# LEDSyncDRVG2.net
KiCad netlist of a schematic drawn in EAGLE
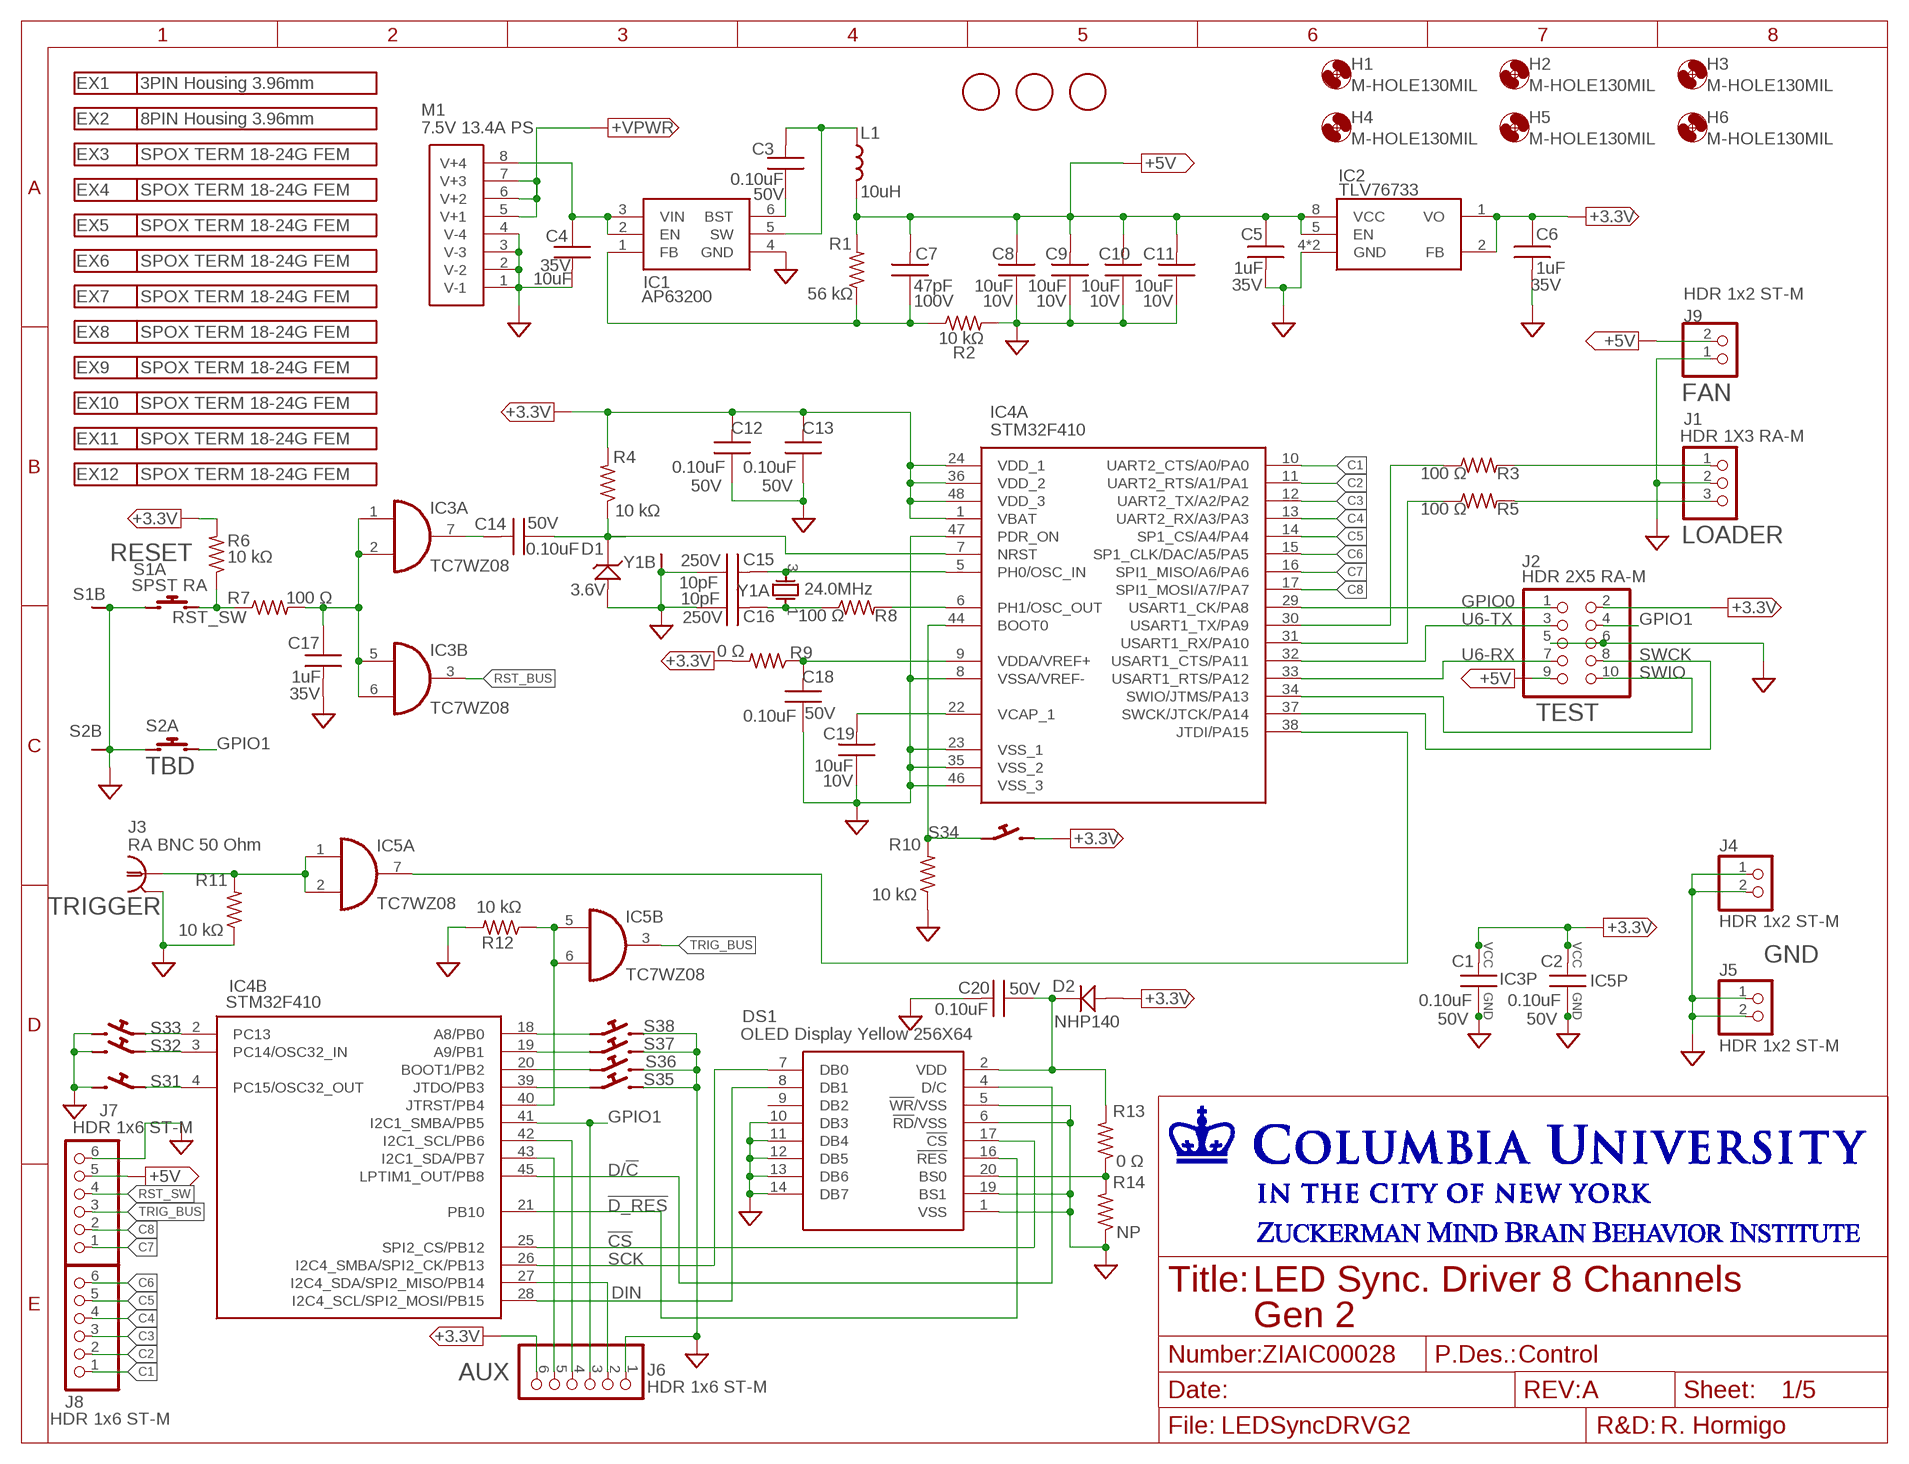
[diagram p0: schematic, sheet 1]
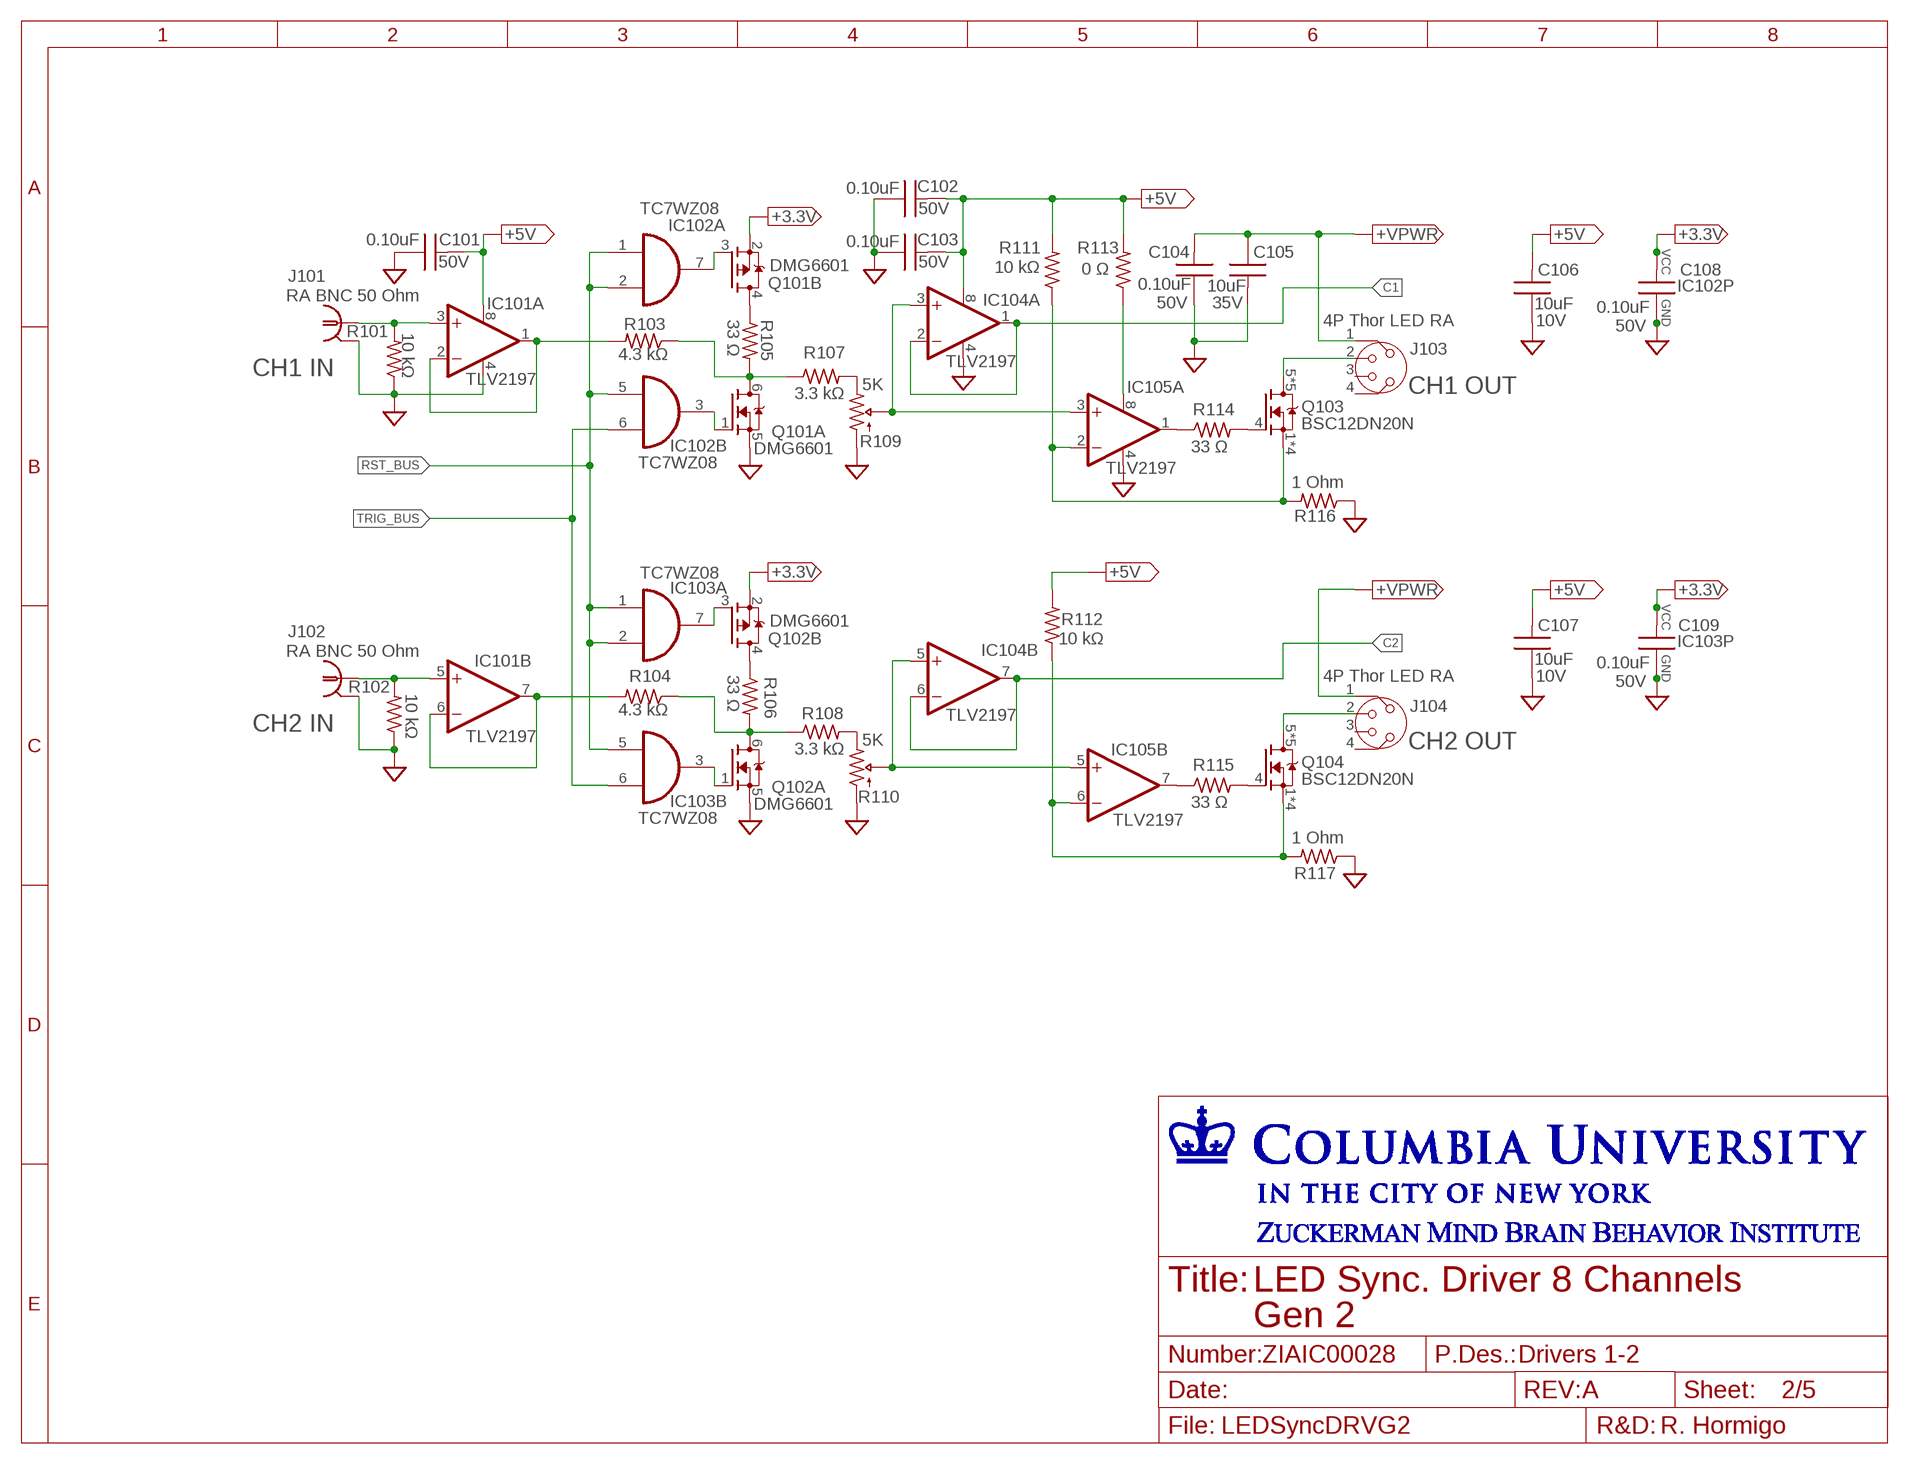
[diagram p1: schematic, sheet 2]
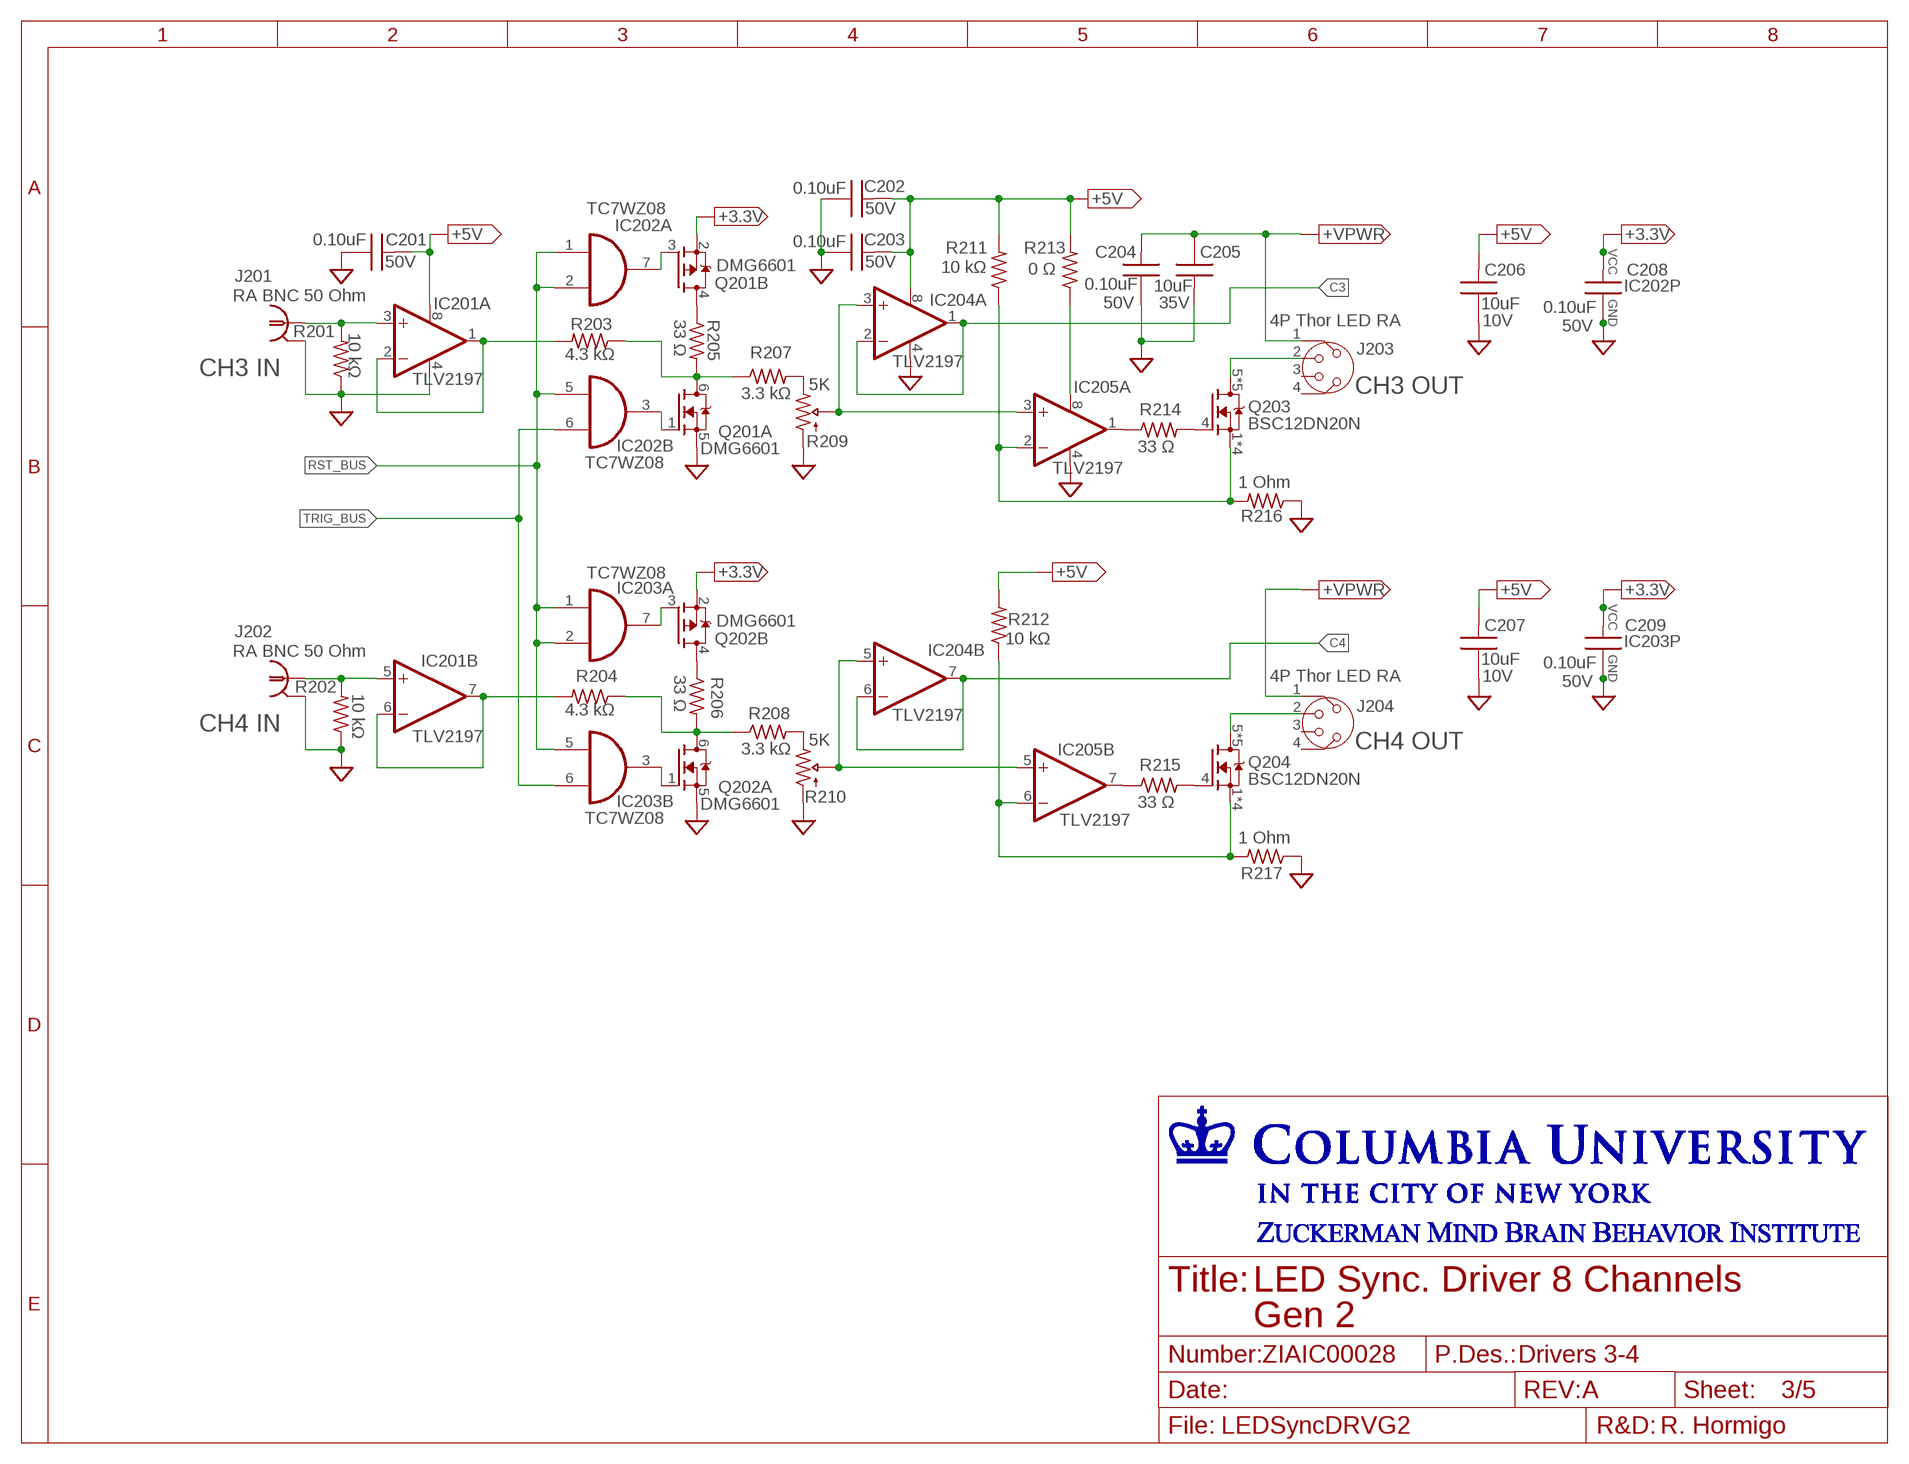
[diagram p2: schematic, sheet 3]
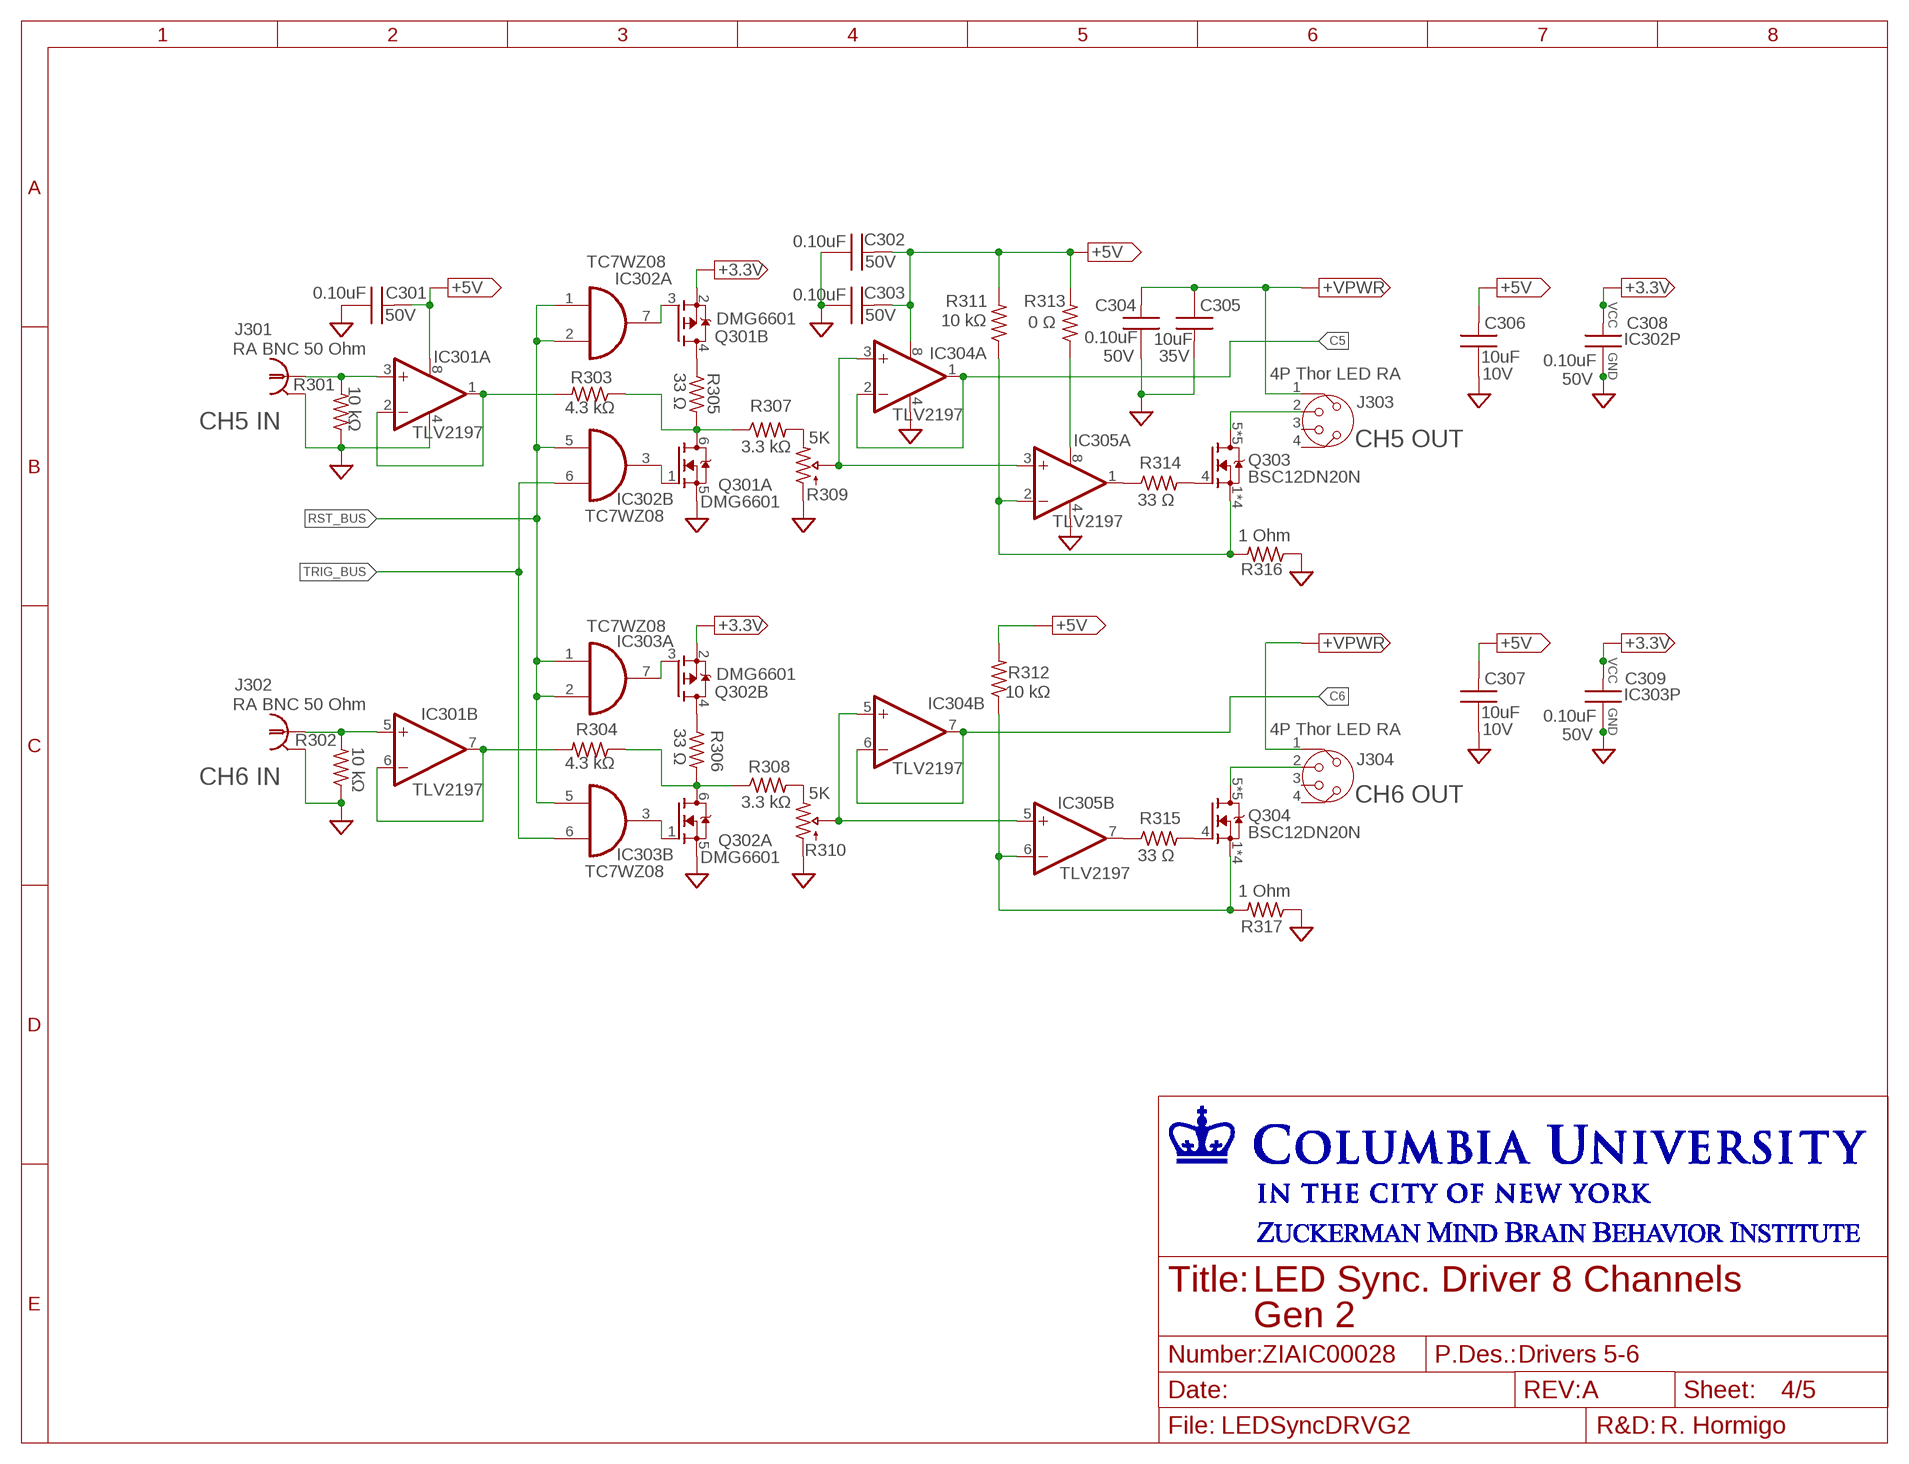
[diagram p3: schematic, sheet 4]
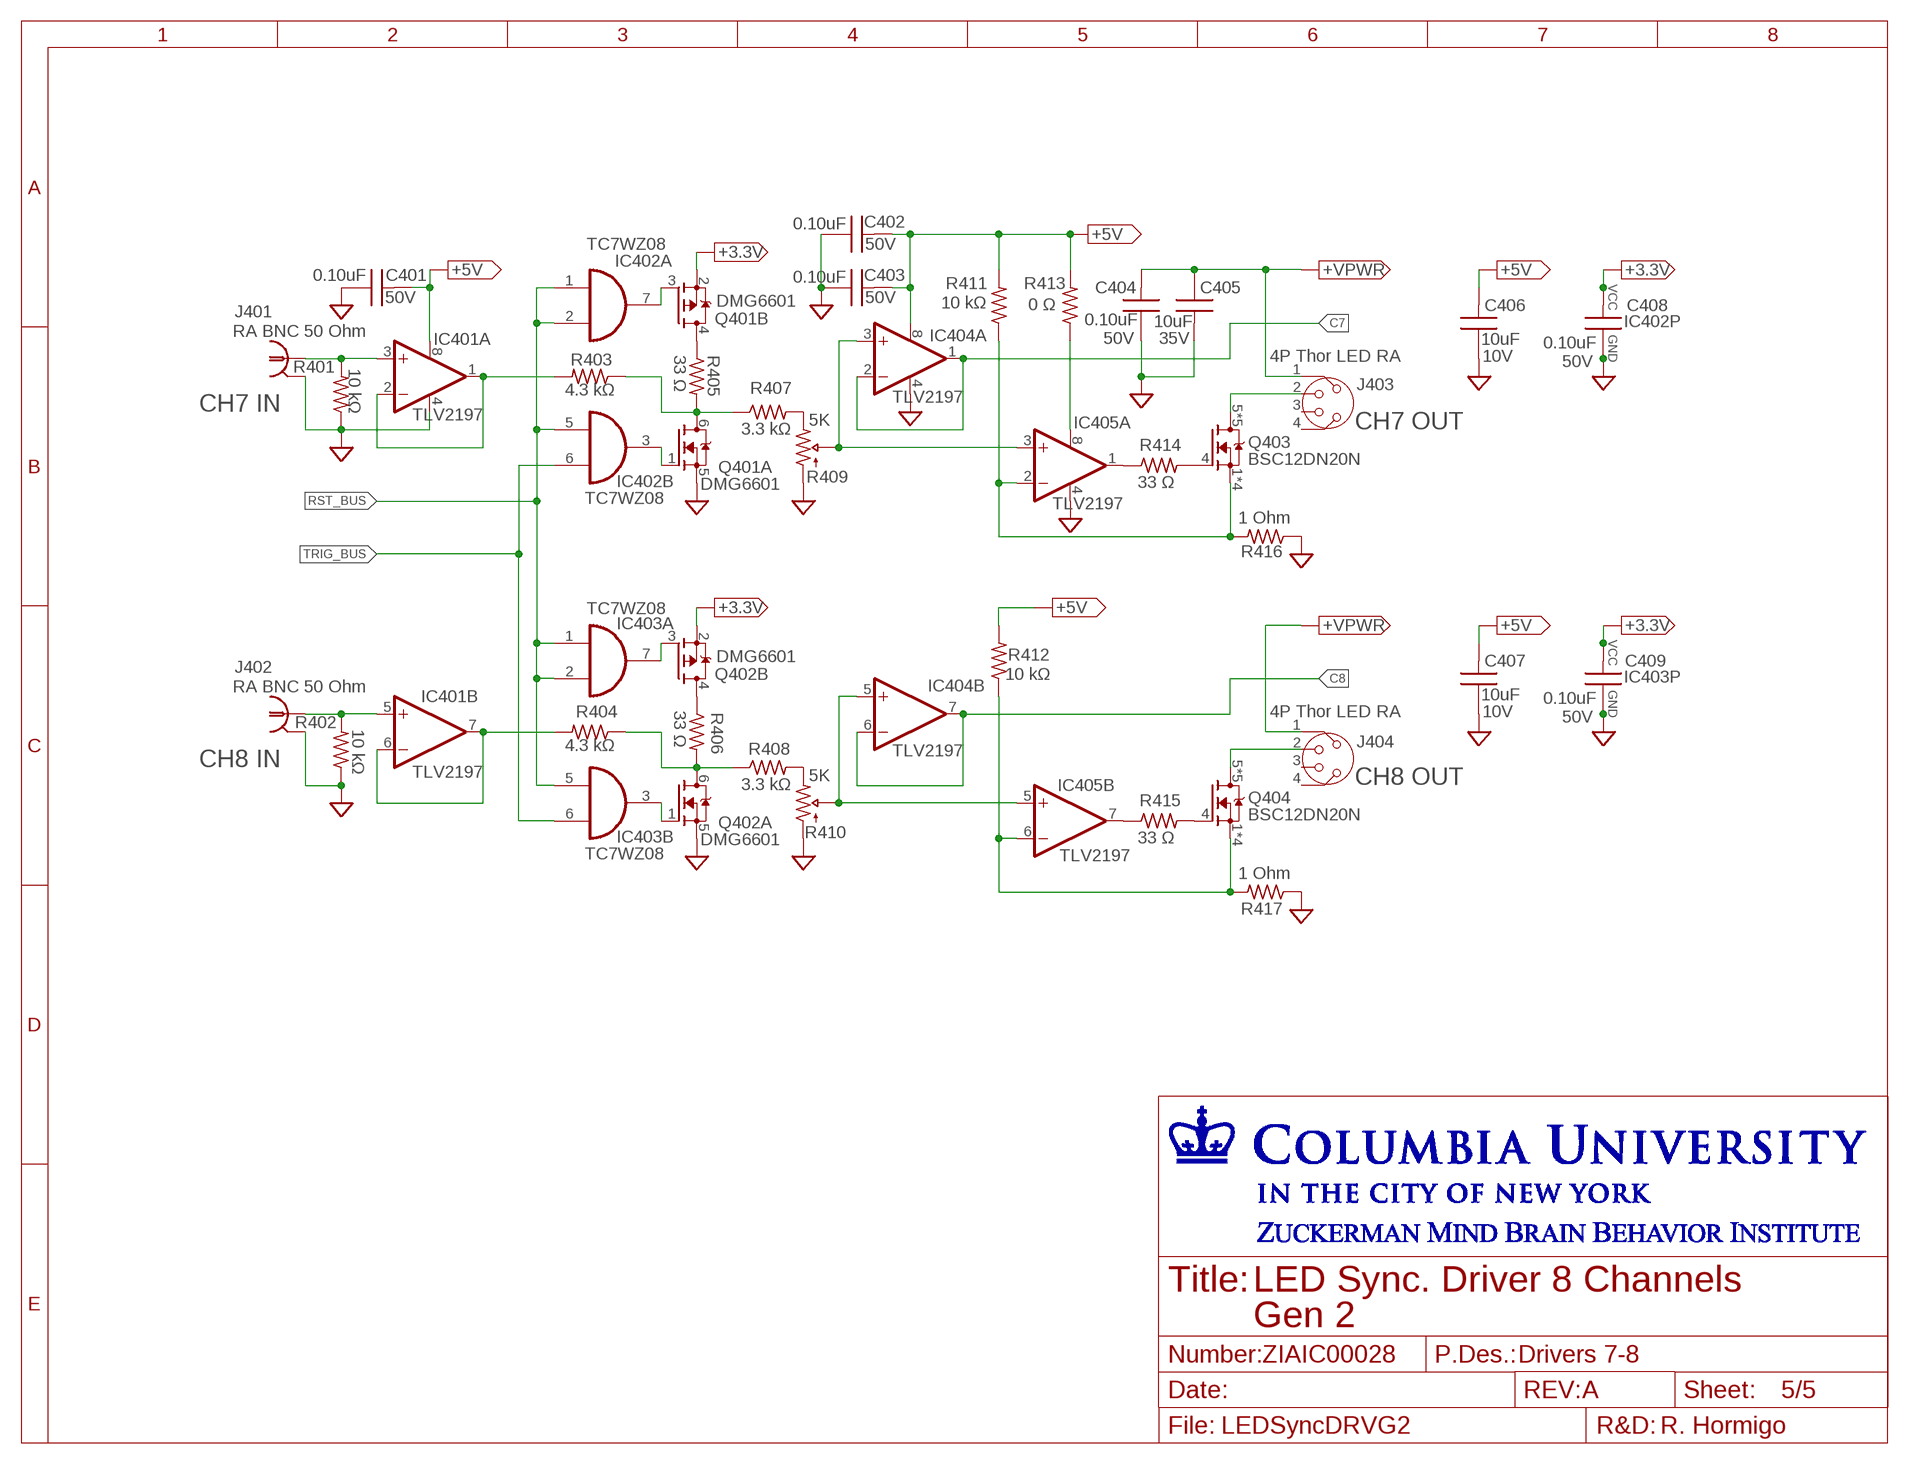
[diagram p4: schematic, sheet 5]

(export (version "E")
  (design (tool "Eeschema 10.0.6"))
  (components
    (comp (ref "C101")
      (value "0.10uF")
      (footprint "eagle-import:MLCC_0603")
      (fields
        (field (name "MPN") "06035C104JAT2A")
        (field (name "TOLERANCE") "5%")
        (field (name "VOLTAGE") "50V")
      )
      (libsource (lib "eagle-import") (part "MLCC_0603_100N"))
    )
    (comp (ref "C102")
      (value "0.10uF")
      (footprint "eagle-import:MLCC_0603")
      (fields
        (field (name "MPN") "06035C104JAT2A")
        (field (name "TOLERANCE") "5%")
        (field (name "VOLTAGE") "50V")
      )
      (libsource (lib "eagle-import") (part "MLCC_0603_100N"))
    )
    (comp (ref "C103")
      (value "0.10uF")
      (footprint "eagle-import:MLCC_0603")
      (fields
        (field (name "MPN") "06035C104JAT2A")
        (field (name "TOLERANCE") "5%")
        (field (name "VOLTAGE") "50V")
      )
      (libsource (lib "eagle-import") (part "MLCC_0603_100N"))
    )
    (comp (ref "C104")
      (value "0.10uF")
      (footprint "eagle-import:MLCC_0603")
      (fields
        (field (name "MPN") "06035C104JAT2A")
        (field (name "TOLERANCE") "5%")
        (field (name "VOLTAGE") "50V")
      )
      (libsource (lib "eagle-import") (part "MLCC_0603_100N"))
    )
    (comp (ref "C105")
      (value "10uF")
      (footprint "eagle-import:MLCC_1206")
      (fields (field (name "VOLTAGE") "35V") (field (name "MPN") "GMK316AB7106KL-TR"))
      (libsource (lib "eagle-import") (part "MLCC1206_"))
    )
    (comp (ref "C106")
      (value "10uF")
      (footprint "eagle-import:MLCC_0603")
      (fields
        (field (name "MPN") "0603ZD106KAT2A")
        (field (name "TOLERANCE") "10%")
        (field (name "VOLTAGE") "10V")
      )
      (libsource (lib "eagle-import") (part "MLCC_0603_10UF-10V"))
    )
    (comp (ref "C107")
      (value "10uF")
      (footprint "eagle-import:MLCC_0603")
      (fields
        (field (name "MPN") "0603ZD106KAT2A")
        (field (name "TOLERANCE") "10%")
        (field (name "VOLTAGE") "10V")
      )
      (libsource (lib "eagle-import") (part "MLCC_0603_10UF-10V"))
    )
    (comp (ref "C108")
      (value "0.10uF")
      (footprint "eagle-import:MLCC_0603")
      (fields
        (field (name "MPN") "06035C104JAT2A")
        (field (name "TOLERANCE") "5%")
        (field (name "VOLTAGE") "50V")
      )
      (libsource (lib "eagle-import") (part "MLCC_0603_100N"))
    )
    (comp (ref "C109")
      (value "0.10uF")
      (footprint "eagle-import:MLCC_0603")
      (fields
        (field (name "MPN") "06035C104JAT2A")
        (field (name "TOLERANCE") "5%")
        (field (name "VOLTAGE") "50V")
      )
      (libsource (lib "eagle-import") (part "MLCC_0603_100N"))
    )
    (comp (ref "IC101")
      (value "TLV2197")
      (footprint "eagle-import:VSSOP8-DGK-065P")
      (fields (field (name "MPN") "TLV2197QDGKRQ1"))
      (libsource (lib "eagle-import") (part "OPA_D_TLV2172IDGKRTLV2197QDGK"))
    )
    (comp (ref "IC102")
      (value "TC7WZ08")
      (footprint "eagle-import:SOP50P310X90-8N")
      (fields (field (name "MPN") "TC7WZ08FK"))
      (libsource (lib "eagle-import") (part "AND2_TSOP8"))
    )
    (comp (ref "IC103")
      (value "TC7WZ08")
      (footprint "eagle-import:SOP50P310X90-8N")
      (fields (field (name "MPN") "TC7WZ08FK"))
      (libsource (lib "eagle-import") (part "AND2_TSOP8"))
    )
    (comp (ref "IC104")
      (value "TLV2197")
      (footprint "eagle-import:VSSOP8-DGK-065P")
      (fields (field (name "MPN") "TLV2197QDGKRQ1"))
      (libsource (lib "eagle-import") (part "OPA_D_TLV2172IDGKRTLV2197QDGK"))
    )
    (comp (ref "IC105")
      (value "TLV2197")
      (footprint "eagle-import:VSSOP8-DGK-065P")
      (fields (field (name "MPN") "TLV2197QDGKRQ1"))
      (libsource (lib "eagle-import") (part "OPA_D_TLV2172IDGKRTLV2197QDGK"))
    )
    (comp (ref "J101")
      (value "RA BNC 50 Ohm")
      (footprint "eagle-import:BNC_AMP_227161")
      (fields (field (name "MPN") "5227161-6"))
      (libsource (lib "eagle-import") (part "BNC-4P"))
    )
    (comp (ref "J102")
      (value "RA BNC 50 Ohm")
      (footprint "eagle-import:BNC_AMP_227161")
      (fields (field (name "MPN") "5227161-6"))
      (libsource (lib "eagle-import") (part "BNC-4P"))
    )
    (comp (ref "J103")
      (value "4P Thor LED RA")
      (footprint "eagle-import:CIR_PHX4P_RA")
      (fields (field (name "MPN") "1526169"))
      (libsource (lib "eagle-import") (part "CIRCULAR-4P-THOR-F"))
    )
    (comp (ref "J104")
      (value "4P Thor LED RA")
      (footprint "eagle-import:CIR_PHX4P_RA")
      (fields (field (name "MPN") "1526169"))
      (libsource (lib "eagle-import") (part "CIRCULAR-4P-THOR-F"))
    )
    (comp (ref "Q101")
      (value "DMG6601")
      (footprint "eagle-import:SOT95P280X100-6N")
      (fields (field (name "MPN") "DMG6601LVT-7"))
      (libsource (lib "eagle-import") (part "MOSFET-PN"))
    )
    (comp (ref "Q102")
      (value "DMG6601")
      (footprint "eagle-import:SOT95P280X100-6N")
      (fields (field (name "MPN") "DMG6601LVT-7"))
      (libsource (lib "eagle-import") (part "MOSFET-PN"))
    )
    (comp (ref "Q103")
      (value "BSC12DN20N")
      (footprint "eagle-import:TDSON-8")
      (fields (field (name "MPN") "BSC12DN20NS3 G") (field (name "POWER") "50W"))
      (libsource (lib "eagle-import") (part "MOSFET-NN-MOSFETBSC12DN20NS3G"))
    )
    (comp (ref "Q104")
      (value "BSC12DN20N")
      (footprint "eagle-import:TDSON-8")
      (fields (field (name "MPN") "BSC12DN20NS3 G") (field (name "POWER") "50W"))
      (libsource (lib "eagle-import") (part "MOSFET-NN-MOSFETBSC12DN20NS3G"))
    )
    (comp (ref "R101")
      (value "10 kΩ")
      (footprint "eagle-import:R0603")
      (fields
        (field (name "MPN") "CRCW060310K0FKEA")
        (field (name "POWER") "0.1W")
        (field (name "TOLERANCE") "1%")
      )
      (libsource (lib "eagle-import") (part "RES_0603_10K0"))
    )
    (comp (ref "R102")
      (value "10 kΩ")
      (footprint "eagle-import:R0603")
      (fields
        (field (name "MPN") "CRCW060310K0FKEA")
        (field (name "POWER") "0.1W")
        (field (name "TOLERANCE") "1%")
      )
      (libsource (lib "eagle-import") (part "RES_0603_10K0"))
    )
    (comp (ref "R103")
      (value "4.3 kΩ")
      (footprint "eagle-import:R0603")
      (fields
        (field (name "MPN") "CRCW06034K30FKEA")
        (field (name "POWER") "0.1W")
        (field (name "TOLERANCE") "1%")
      )
      (libsource (lib "eagle-import") (part "RES_0603_4K30"))
    )
    (comp (ref "R104")
      (value "4.3 kΩ")
      (footprint "eagle-import:R0603")
      (fields
        (field (name "MPN") "CRCW06034K30FKEA")
        (field (name "POWER") "0.1W")
        (field (name "TOLERANCE") "1%")
      )
      (libsource (lib "eagle-import") (part "RES_0603_4K30"))
    )
    (comp (ref "R105")
      (value "33 Ω")
      (footprint "eagle-import:R0603")
      (fields
        (field (name "MPN") "CRCW060333R0FKEA")
        (field (name "POWER") "0.1W")
        (field (name "TOLERANCE") "1%")
      )
      (libsource (lib "eagle-import") (part "RES_0603_33R0"))
    )
    (comp (ref "R106")
      (value "33 Ω")
      (footprint "eagle-import:R0603")
      (fields
        (field (name "MPN") "CRCW060333R0FKEA")
        (field (name "POWER") "0.1W")
        (field (name "TOLERANCE") "1%")
      )
      (libsource (lib "eagle-import") (part "RES_0603_33R0"))
    )
    (comp (ref "R107")
      (value "3.3 kΩ")
      (footprint "eagle-import:R0603")
      (fields
        (field (name "MPN") "CRCW06033K30FKEA")
        (field (name "POWER") "0.1W")
        (field (name "TOLERANCE") "1%")
      )
      (libsource (lib "eagle-import") (part "RES_0603_3K30"))
    )
    (comp (ref "R108")
      (value "3.3 kΩ")
      (footprint "eagle-import:R0603")
      (fields
        (field (name "MPN") "CRCW06033K30FKEA")
        (field (name "POWER") "0.1W")
        (field (name "TOLERANCE") "1%")
      )
      (libsource (lib "eagle-import") (part "RES_0603_3K30"))
    )
    (comp (ref "R109")
      (value "5K")
      (footprint "eagle-import:MTBOURNS_RA_LONG")
      (fields (field (name "MPN") "3006P-7-502LF"))
      (libsource (lib "eagle-import") (part "RES_TRIM_5K_RA_MTURN"))
    )
    (comp (ref "R110")
      (value "5K")
      (footprint "eagle-import:MTBOURNS_RA_LONG")
      (fields (field (name "MPN") "3006P-7-502LF"))
      (libsource (lib "eagle-import") (part "RES_TRIM_5K_RA_MTURN"))
    )
    (comp (ref "R111")
      (value "10 kΩ")
      (footprint "eagle-import:R0603")
      (fields
        (field (name "MPN") "CRCW060310K0FKEA")
        (field (name "POWER") "0.1W")
        (field (name "TOLERANCE") "1%")
      )
      (libsource (lib "eagle-import") (part "RES_0603_10K0"))
    )
    (comp (ref "R112")
      (value "10 kΩ")
      (footprint "eagle-import:R0603")
      (fields
        (field (name "MPN") "CRCW060310K0FKEA")
        (field (name "POWER") "0.1W")
        (field (name "TOLERANCE") "1%")
      )
      (libsource (lib "eagle-import") (part "RES_0603_10K0"))
    )
    (comp (ref "R113")
      (value "0 Ω")
      (footprint "eagle-import:R0603")
      (fields (field (name "MPN") "CRCW06030000Z0EA"))
      (libsource (lib "eagle-import") (part "RES_0603_0000"))
    )
    (comp (ref "R114")
      (value "33 Ω")
      (footprint "eagle-import:R0603")
      (fields
        (field (name "MPN") "CRCW060333R0FKEA")
        (field (name "POWER") "0.1W")
        (field (name "TOLERANCE") "1%")
      )
      (libsource (lib "eagle-import") (part "RES_0603_33R0"))
    )
    (comp (ref "R115")
      (value "33 Ω")
      (footprint "eagle-import:R0603")
      (fields
        (field (name "MPN") "CRCW060333R0FKEA")
        (field (name "POWER") "0.1W")
        (field (name "TOLERANCE") "1%")
      )
      (libsource (lib "eagle-import") (part "RES_0603_33R0"))
    )
    (comp (ref "R116")
      (value "1 Ohm")
      (footprint "eagle-import:R1225")
      (fields (field (name "MPN") "WK73S3A3TTE1R00F"))
      (libsource (lib "eagle-import") (part "RES_1225_"))
    )
    (comp (ref "R117")
      (value "1 Ohm")
      (footprint "eagle-import:R1225")
      (fields (field (name "MPN") "WK73S3A3TTE1R00F"))
      (libsource (lib "eagle-import") (part "RES_1225_"))
    )
    (comp (ref "C301")
      (value "0.10uF")
      (footprint "eagle-import:MLCC_0603")
      (fields
        (field (name "MPN") "06035C104JAT2A")
        (field (name "TOLERANCE") "5%")
        (field (name "VOLTAGE") "50V")
      )
      (libsource (lib "eagle-import") (part "MLCC_0603_100N"))
    )
    (comp (ref "C302")
      (value "0.10uF")
      (footprint "eagle-import:MLCC_0603")
      (fields
        (field (name "MPN") "06035C104JAT2A")
        (field (name "TOLERANCE") "5%")
        (field (name "VOLTAGE") "50V")
      )
      (libsource (lib "eagle-import") (part "MLCC_0603_100N"))
    )
    (comp (ref "C303")
      (value "0.10uF")
      (footprint "eagle-import:MLCC_0603")
      (fields
        (field (name "MPN") "06035C104JAT2A")
        (field (name "TOLERANCE") "5%")
        (field (name "VOLTAGE") "50V")
      )
      (libsource (lib "eagle-import") (part "MLCC_0603_100N"))
    )
    (comp (ref "C304")
      (value "0.10uF")
      (footprint "eagle-import:MLCC_0603")
      (fields
        (field (name "MPN") "06035C104JAT2A")
        (field (name "TOLERANCE") "5%")
        (field (name "VOLTAGE") "50V")
      )
      (libsource (lib "eagle-import") (part "MLCC_0603_100N"))
    )
    (comp (ref "C305")
      (value "10uF")
      (footprint "eagle-import:MLCC_1206")
      (fields (field (name "VOLTAGE") "35V") (field (name "MPN") "GMK316AB7106KL-TR"))
      (libsource (lib "eagle-import") (part "MLCC1206_"))
    )
    (comp (ref "C306")
      (value "10uF")
      (footprint "eagle-import:MLCC_0603")
      (fields
        (field (name "MPN") "0603ZD106KAT2A")
        (field (name "TOLERANCE") "10%")
        (field (name "VOLTAGE") "10V")
      )
      (libsource (lib "eagle-import") (part "MLCC_0603_10UF-10V"))
    )
    (comp (ref "C307")
      (value "10uF")
      (footprint "eagle-import:MLCC_0603")
      (fields
        (field (name "MPN") "0603ZD106KAT2A")
        (field (name "TOLERANCE") "10%")
        (field (name "VOLTAGE") "10V")
      )
      (libsource (lib "eagle-import") (part "MLCC_0603_10UF-10V"))
    )
    (comp (ref "C308")
      (value "0.10uF")
      (footprint "eagle-import:MLCC_0603")
      (fields
        (field (name "MPN") "06035C104JAT2A")
        (field (name "TOLERANCE") "5%")
        (field (name "VOLTAGE") "50V")
      )
      (libsource (lib "eagle-import") (part "MLCC_0603_100N"))
    )
    (comp (ref "C309")
      (value "0.10uF")
      (footprint "eagle-import:MLCC_0603")
      (fields
        (field (name "MPN") "06035C104JAT2A")
        (field (name "TOLERANCE") "5%")
        (field (name "VOLTAGE") "50V")
      )
      (libsource (lib "eagle-import") (part "MLCC_0603_100N"))
    )
    (comp (ref "IC301")
      (value "TLV2197")
      (footprint "eagle-import:VSSOP8-DGK-065P")
      (fields (field (name "MPN") "TLV2197QDGKRQ1"))
      (libsource (lib "eagle-import") (part "OPA_D_TLV2172IDGKRTLV2197QDGK"))
    )
    (comp (ref "IC302")
      (value "TC7WZ08")
      (footprint "eagle-import:SOP50P310X90-8N")
      (fields (field (name "MPN") "TC7WZ08FK"))
      (libsource (lib "eagle-import") (part "AND2_TSOP8"))
    )
    (comp (ref "IC303")
      (value "TC7WZ08")
      (footprint "eagle-import:SOP50P310X90-8N")
      (fields (field (name "MPN") "TC7WZ08FK"))
      (libsource (lib "eagle-import") (part "AND2_TSOP8"))
    )
    (comp (ref "IC304")
      (value "TLV2197")
      (footprint "eagle-import:VSSOP8-DGK-065P")
      (fields (field (name "MPN") "TLV2197QDGKRQ1"))
      (libsource (lib "eagle-import") (part "OPA_D_TLV2172IDGKRTLV2197QDGK"))
    )
    (comp (ref "IC305")
      (value "TLV2197")
      (footprint "eagle-import:VSSOP8-DGK-065P")
      (fields (field (name "MPN") "TLV2197QDGKRQ1"))
      (libsource (lib "eagle-import") (part "OPA_D_TLV2172IDGKRTLV2197QDGK"))
    )
    (comp (ref "J301")
      (value "RA BNC 50 Ohm")
      (footprint "eagle-import:BNC_AMP_227161")
      (fields (field (name "MPN") "5227161-6"))
      (libsource (lib "eagle-import") (part "BNC-4P"))
    )
    (comp (ref "J302")
      (value "RA BNC 50 Ohm")
      (footprint "eagle-import:BNC_AMP_227161")
      (fields (field (name "MPN") "5227161-6"))
      (libsource (lib "eagle-import") (part "BNC-4P"))
    )
    (comp (ref "J303")
      (value "4P Thor LED RA")
      (footprint "eagle-import:CIR_PHX4P_RA")
      (fields (field (name "MPN") "1526169"))
      (libsource (lib "eagle-import") (part "CIRCULAR-4P-THOR-F"))
    )
    (comp (ref "J304")
      (value "4P Thor LED RA")
      (footprint "eagle-import:CIR_PHX4P_RA")
      (fields (field (name "MPN") "1526169"))
      (libsource (lib "eagle-import") (part "CIRCULAR-4P-THOR-F"))
    )
    (comp (ref "Q301")
      (value "DMG6601")
      (footprint "eagle-import:SOT95P280X100-6N")
      (fields (field (name "MPN") "DMG6601LVT-7"))
      (libsource (lib "eagle-import") (part "MOSFET-PN"))
    )
    (comp (ref "Q302")
      (value "DMG6601")
      (footprint "eagle-import:SOT95P280X100-6N")
      (fields (field (name "MPN") "DMG6601LVT-7"))
      (libsource (lib "eagle-import") (part "MOSFET-PN"))
    )
    (comp (ref "Q303")
      (value "BSC12DN20N")
      (footprint "eagle-import:TDSON-8")
      (fields (field (name "MPN") "BSC12DN20NS3 G") (field (name "POWER") "50W"))
      (libsource (lib "eagle-import") (part "MOSFET-NN-MOSFETBSC12DN20NS3G"))
    )
    (comp (ref "Q304")
      (value "BSC12DN20N")
      (footprint "eagle-import:TDSON-8")
      (fields (field (name "MPN") "BSC12DN20NS3 G") (field (name "POWER") "50W"))
      (libsource (lib "eagle-import") (part "MOSFET-NN-MOSFETBSC12DN20NS3G"))
    )
    (comp (ref "R301")
      (value "10 kΩ")
      (footprint "eagle-import:R0603")
      (fields
        (field (name "MPN") "CRCW060310K0FKEA")
        (field (name "POWER") "0.1W")
        (field (name "TOLERANCE") "1%")
      )
      (libsource (lib "eagle-import") (part "RES_0603_10K0"))
    )
    (comp (ref "R302")
      (value "10 kΩ")
      (footprint "eagle-import:R0603")
      (fields
        (field (name "MPN") "CRCW060310K0FKEA")
        (field (name "POWER") "0.1W")
        (field (name "TOLERANCE") "1%")
      )
      (libsource (lib "eagle-import") (part "RES_0603_10K0"))
    )
    (comp (ref "R303")
      (value "4.3 kΩ")
      (footprint "eagle-import:R0603")
      (fields
        (field (name "MPN") "CRCW06034K30FKEA")
        (field (name "POWER") "0.1W")
        (field (name "TOLERANCE") "1%")
      )
      (libsource (lib "eagle-import") (part "RES_0603_4K30"))
    )
    (comp (ref "R304")
      (value "4.3 kΩ")
      (footprint "eagle-import:R0603")
      (fields
        (field (name "MPN") "CRCW06034K30FKEA")
        (field (name "POWER") "0.1W")
        (field (name "TOLERANCE") "1%")
      )
      (libsource (lib "eagle-import") (part "RES_0603_4K30"))
    )
    (comp (ref "R305")
      (value "33 Ω")
      (footprint "eagle-import:R0603")
      (fields
        (field (name "MPN") "CRCW060333R0FKEA")
        (field (name "POWER") "0.1W")
        (field (name "TOLERANCE") "1%")
      )
      (libsource (lib "eagle-import") (part "RES_0603_33R0"))
    )
    (comp (ref "R306")
      (value "33 Ω")
      (footprint "eagle-import:R0603")
      (fields
        (field (name "MPN") "CRCW060333R0FKEA")
        (field (name "POWER") "0.1W")
        (field (name "TOLERANCE") "1%")
      )
      (libsource (lib "eagle-import") (part "RES_0603_33R0"))
    )
    (comp (ref "R307")
      (value "3.3 kΩ")
      (footprint "eagle-import:R0603")
      (fields
        (field (name "MPN") "CRCW06033K30FKEA")
        (field (name "POWER") "0.1W")
        (field (name "TOLERANCE") "1%")
      )
      (libsource (lib "eagle-import") (part "RES_0603_3K30"))
    )
    (comp (ref "R308")
      (value "3.3 kΩ")
      (footprint "eagle-import:R0603")
      (fields
        (field (name "MPN") "CRCW06033K30FKEA")
        (field (name "POWER") "0.1W")
        (field (name "TOLERANCE") "1%")
      )
      (libsource (lib "eagle-import") (part "RES_0603_3K30"))
    )
    (comp (ref "R309")
      (value "5K")
      (footprint "eagle-import:MTBOURNS_RA_LONG")
      (fields (field (name "MPN") "3006P-7-502LF"))
      (libsource (lib "eagle-import") (part "RES_TRIM_5K_RA_MTURN"))
    )
    (comp (ref "R310")
      (value "5K")
      (footprint "eagle-import:MTBOURNS_RA_LONG")
      (fields (field (name "MPN") "3006P-7-502LF"))
      (libsource (lib "eagle-import") (part "RES_TRIM_5K_RA_MTURN"))
    )
    (comp (ref "R311")
      (value "10 kΩ")
      (footprint "eagle-import:R0603")
      (fields
        (field (name "MPN") "CRCW060310K0FKEA")
        (field (name "POWER") "0.1W")
        (field (name "TOLERANCE") "1%")
      )
      (libsource (lib "eagle-import") (part "RES_0603_10K0"))
    )
    (comp (ref "R312")
      (value "10 kΩ")
      (footprint "eagle-import:R0603")
      (fields
        (field (name "MPN") "CRCW060310K0FKEA")
        (field (name "POWER") "0.1W")
        (field (name "TOLERANCE") "1%")
      )
      (libsource (lib "eagle-import") (part "RES_0603_10K0"))
    )
    (comp (ref "R313")
      (value "0 Ω")
      (footprint "eagle-import:R0603")
      (fields (field (name "MPN") "CRCW06030000Z0EA"))
      (libsource (lib "eagle-import") (part "RES_0603_0000"))
    )
    (comp (ref "R314")
      (value "33 Ω")
      (footprint "eagle-import:R0603")
      (fields
        (field (name "MPN") "CRCW060333R0FKEA")
        (field (name "POWER") "0.1W")
        (field (name "TOLERANCE") "1%")
      )
      (libsource (lib "eagle-import") (part "RES_0603_33R0"))
    )
    (comp (ref "R315")
      (value "33 Ω")
      (footprint "eagle-import:R0603")
      (fields
        (field (name "MPN") "CRCW060333R0FKEA")
        (field (name "POWER") "0.1W")
        (field (name "TOLERANCE") "1%")
      )
      (libsource (lib "eagle-import") (part "RES_0603_33R0"))
    )
    (comp (ref "R316")
      (value "1 Ohm")
      (footprint "eagle-import:R1225")
      (fields (field (name "MPN") "WK73S3A3TTE1R00F"))
      (libsource (lib "eagle-import") (part "RES_1225_"))
    )
    (comp (ref "R317")
      (value "1 Ohm")
      (footprint "eagle-import:R1225")
      (fields (field (name "MPN") "WK73S3A3TTE1R00F"))
      (libsource (lib "eagle-import") (part "RES_1225_"))
    )
    (comp (ref "C1")
      (value "0.10uF")
      (footprint "eagle-import:MLCC_0603")
      (fields
        (field (name "MPN") "06035C104JAT2A")
        (field (name "TOLERANCE") "5%")
        (field (name "VOLTAGE") "50V")
      )
      (libsource (lib "eagle-import") (part "MLCC_0603_100N"))
    )
    (comp (ref "C2")
      (value "0.10uF")
      (footprint "eagle-import:MLCC_0603")
      (fields
        (field (name "MPN") "06035C104JAT2A")
        (field (name "TOLERANCE") "5%")
        (field (name "VOLTAGE") "50V")
      )
      (libsource (lib "eagle-import") (part "MLCC_0603_100N"))
    )
    (comp (ref "C3")
      (value "0.10uF")
      (footprint "eagle-import:MLCC_0603")
      (fields
        (field (name "MPN") "06035C104JAT2A")
        (field (name "TOLERANCE") "5%")
        (field (name "VOLTAGE") "50V")
      )
      (libsource (lib "eagle-import") (part "MLCC_0603_100N"))
    )
    (comp (ref "C4")
      (value "10uF")
      (footprint "eagle-import:MLCC_1206")
      (fields (field (name "VOLTAGE") "35V") (field (name "MPN") "GMK316AB7106KL-TR"))
      (libsource (lib "eagle-import") (part "MLCC1206_"))
    )
    (comp (ref "C5")
      (value "1uF")
      (footprint "eagle-import:MLCC_0603")
      (fields
        (field (name "MPN") "CGA3E1X7R1V105K080AC")
        (field (name "TOLERANCE") "10%")
        (field (name "VOLTAGE") "35V")
      )
      (libsource (lib "eagle-import") (part "MLCC_0603_1UF"))
    )
    (comp (ref "C6")
      (value "1uF")
      (footprint "eagle-import:MLCC_0603")
      (fields
        (field (name "MPN") "CGA3E1X7R1V105K080AC")
        (field (name "TOLERANCE") "10%")
        (field (name "VOLTAGE") "35V")
      )
      (libsource (lib "eagle-import") (part "MLCC_0603_1UF"))
    )
    (comp (ref "C7")
      (value "47pF")
      (footprint "eagle-import:MLCC_0603")
      (fields
        (field (name "MPN") "GCM1885C2A470FA16D")
        (field (name "TOLERANCE") "1%")
        (field (name "VOLTAGE") "100V")
      )
      (libsource (lib "eagle-import") (part "MLCC_0603_47P"))
    )
    (comp (ref "C8")
      (value "10uF")
      (footprint "eagle-import:MLCC_0603")
      (fields
        (field (name "MPN") "0603ZD106KAT2A")
        (field (name "TOLERANCE") "10%")
        (field (name "VOLTAGE") "10V")
      )
      (libsource (lib "eagle-import") (part "MLCC_0603_10UF-10V"))
    )
    (comp (ref "C9")
      (value "10uF")
      (footprint "eagle-import:MLCC_0603")
      (fields
        (field (name "MPN") "0603ZD106KAT2A")
        (field (name "TOLERANCE") "10%")
        (field (name "VOLTAGE") "10V")
      )
      (libsource (lib "eagle-import") (part "MLCC_0603_10UF-10V"))
    )
    (comp (ref "C10")
      (value "10uF")
      (footprint "eagle-import:MLCC_0603")
      (fields
        (field (name "MPN") "0603ZD106KAT2A")
        (field (name "TOLERANCE") "10%")
        (field (name "VOLTAGE") "10V")
      )
      (libsource (lib "eagle-import") (part "MLCC_0603_10UF-10V"))
    )
    (comp (ref "C11")
      (value "10uF")
      (footprint "eagle-import:MLCC_0603")
      (fields
        (field (name "MPN") "0603ZD106KAT2A")
        (field (name "TOLERANCE") "10%")
        (field (name "VOLTAGE") "10V")
      )
      (libsource (lib "eagle-import") (part "MLCC_0603_10UF-10V"))
    )
    (comp (ref "C12")
      (value "0.10uF")
      (footprint "eagle-import:MLCC_0603")
      (fields
        (field (name "MPN") "06035C104JAT2A")
        (field (name "TOLERANCE") "5%")
        (field (name "VOLTAGE") "50V")
      )
      (libsource (lib "eagle-import") (part "MLCC_0603_100N"))
    )
    (comp (ref "C13")
      (value "0.10uF")
      (footprint "eagle-import:MLCC_0603")
      (fields
        (field (name "MPN") "06035C104JAT2A")
        (field (name "TOLERANCE") "5%")
        (field (name "VOLTAGE") "50V")
      )
      (libsource (lib "eagle-import") (part "MLCC_0603_100N"))
    )
    (comp (ref "C14")
      (value "0.10uF")
      (footprint "eagle-import:MLCC_0603")
      (fields
        (field (name "MPN") "06035C104JAT2A")
        (field (name "TOLERANCE") "5%")
        (field (name "VOLTAGE") "50V")
      )
      (libsource (lib "eagle-import") (part "MLCC_0603_100N"))
    )
    (comp (ref "C15")
      (value "10pF")
      (footprint "eagle-import:MLCC_0603")
      (fields
        (field (name "MPN") "VJ0603D100JXPAJ")
        (field (name "TOLERANCE") "5%")
        (field (name "VOLTAGE") "250V")
      )
      (libsource (lib "eagle-import") (part "MLCC_0603_10P"))
    )
    (comp (ref "C16")
      (value "10pF")
      (footprint "eagle-import:MLCC_0603")
      (fields
        (field (name "MPN") "VJ0603D100JXPAJ")
        (field (name "TOLERANCE") "5%")
        (field (name "VOLTAGE") "250V")
      )
      (libsource (lib "eagle-import") (part "MLCC_0603_10P"))
    )
    (comp (ref "C17")
      (value "1uF")
      (footprint "eagle-import:MLCC_0603")
      (fields
        (field (name "MPN") "CGA3E1X7R1V105K080AC")
        (field (name "TOLERANCE") "10%")
        (field (name "VOLTAGE") "35V")
      )
      (libsource (lib "eagle-import") (part "MLCC_0603_1UF"))
    )
    (comp (ref "C18")
      (value "0.10uF")
      (footprint "eagle-import:MLCC_0603")
      (fields
        (field (name "MPN") "06035C104JAT2A")
        (field (name "TOLERANCE") "5%")
        (field (name "VOLTAGE") "50V")
      )
      (libsource (lib "eagle-import") (part "MLCC_0603_100N"))
    )
    (comp (ref "C19")
      (value "10uF")
      (footprint "eagle-import:MLCC_0603")
      (fields
        (field (name "MPN") "0603ZD106KAT2A")
        (field (name "TOLERANCE") "10%")
        (field (name "VOLTAGE") "10V")
      )
      (libsource (lib "eagle-import") (part "MLCC_0603_10UF-10V"))
    )
    (comp (ref "C20")
      (value "0.10uF")
      (footprint "eagle-import:MLCC_0603")
      (fields
        (field (name "MPN") "06035C104JAT2A")
        (field (name "TOLERANCE") "5%")
        (field (name "VOLTAGE") "50V")
      )
      (libsource (lib "eagle-import") (part "MLCC_0603_100N"))
    )
    (comp (ref "D1")
      (value "3.6V")
      (footprint "eagle-import:SOD3716X135N_DIODE")
      (fields (field (name "MPN") "MMSZ3V6T1G") (field (name "POWER") "0.5W max"))
      (libsource (lib "eagle-import") (part "DIODE_ZENERZND3.6V"))
    )
    (comp (ref "D2")
      (value "NHP140")
      (footprint "eagle-import:SOD-123FL")
      (fields (field (name "MPN") "NHP140SFT3G") (field (name "POWER") "330 degC/W"))
      (libsource (lib "eagle-import") (part "DIODE_RECNHP140"))
    )
    (comp (ref "DS1")
      (value "OLED Display Yellow 256X64")
      (footprint "eagle-import:DISPLAY20P")
      (fields (field (name "MPN") "NHD-3.12-25664UCY2"))
      (libsource (lib "eagle-import") (part "DISPLAY20P"))
    )
    (comp (ref "H1")
      (value "M-HOLE130MIL")
      (footprint "eagle-import:4-40_130HOLE_260CLEAR")
      (libsource (lib "eagle-import") (part "M-HOLE130MIL"))
    )
    (comp (ref "H2")
      (value "M-HOLE130MIL")
      (footprint "eagle-import:4-40_130HOLE_260CLEAR")
      (libsource (lib "eagle-import") (part "M-HOLE130MIL"))
    )
    (comp (ref "H3")
      (value "M-HOLE130MIL")
      (footprint "eagle-import:4-40_130HOLE_260CLEAR")
      (libsource (lib "eagle-import") (part "M-HOLE130MIL"))
    )
    (comp (ref "H4")
      (value "M-HOLE130MIL")
      (footprint "eagle-import:4-40_130HOLE_260CLEAR")
      (libsource (lib "eagle-import") (part "M-HOLE130MIL"))
    )
    (comp (ref "H5")
      (value "M-HOLE130MIL")
      (footprint "eagle-import:4-40_130HOLE_260CLEAR")
      (libsource (lib "eagle-import") (part "M-HOLE130MIL"))
    )
    (comp (ref "H6")
      (value "M-HOLE130MIL")
      (footprint "eagle-import:4-40_130HOLE_260CLEAR")
      (libsource (lib "eagle-import") (part "M-HOLE130MIL"))
    )
    (comp (ref "IC1")
      (value "AP63200")
      (footprint "eagle-import:SOT95P280X100-6N")
      (fields (field (name "MPN") "AP63200WU-7"))
      (libsource (lib "eagle-import") (part "AP63200"))
    )
    (comp (ref "IC2")
      (value "TLV76733")
      (footprint "eagle-import:VSSOP8-DGK-065P")
      (fields (field (name "MPN") "TLV76733DGNR"))
      (libsource (lib "eagle-import") (part "LDO8P_TLV76733DGNR"))
    )
    (comp (ref "IC3")
      (value "TC7WZ08")
      (footprint "eagle-import:SOP50P310X90-8N")
      (fields (field (name "MPN") "TC7WZ08FK"))
      (libsource (lib "eagle-import") (part "AND2_TSOP8"))
    )
    (comp (ref "IC4")
      (value "STM32F410")
      (footprint "eagle-import:QFP50P900X900X160-48N")
      (fields (field (name "MPN") "STM32F410CBT3"))
      (libsource (lib "eagle-import") (part "STM32F410C"))
    )
    (comp (ref "IC5")
      (value "TC7WZ08")
      (footprint "eagle-import:SOP50P310X90-8N")
      (fields (field (name "MPN") "TC7WZ08FK"))
      (libsource (lib "eagle-import") (part "AND2_TSOP8"))
    )
    (comp (ref "J1")
      (value "HDR 1X3 RA-M")
      (footprint "eagle-import:HDR_1X3RAS")
      (fields (field (name "MPN") "70555-0072"))
      (libsource (lib "eagle-import") (part "PIN-1X3HDR_1X3RAS_M"))
    )
    (comp (ref "J2")
      (value "HDR 2X5 RA-M")
      (footprint "eagle-import:HDR_2X5M_RAS")
      (fields (field (name "MPN") "30310-5002HB"))
      (libsource (lib "eagle-import") (part "PIN-2X5HDR_2X5RAS_M"))
    )
    (comp (ref "J3")
      (value "RA BNC 50 Ohm")
      (footprint "eagle-import:BNC_AMP_227161")
      (fields (field (name "MPN") "5227161-6"))
      (libsource (lib "eagle-import") (part "BNC-4P"))
    )
    (comp (ref "J4")
      (value "HDR 1x2 ST-M")
      (footprint "eagle-import:HDR_1X2")
      (fields (field (name "MPN") "77311-124-02LF"))
      (libsource (lib "eagle-import") (part "PIN-1X2HDR2STMS"))
    )
    (comp (ref "J5")
      (value "HDR 1x2 ST-M")
      (footprint "eagle-import:HDR_1X2")
      (fields (field (name "MPN") "77311-124-02LF"))
      (libsource (lib "eagle-import") (part "PIN-1X2HDR2STMS"))
    )
    (comp (ref "J6")
      (value "HDR 1x6 ST-M")
      (footprint "eagle-import:HDR_1X06")
      (fields (field (name "MPN") "77311-124-06LF"))
      (libsource (lib "eagle-import") (part "PIN-1X6_6STM"))
    )
    (comp (ref "J7")
      (value "HDR 1x6 ST-M")
      (footprint "eagle-import:HDR_1X06")
      (fields (field (name "MPN") "77311-124-06LF") (field (name "MNF") "NP") (field (name "MPN_1") "NP"))
      (libsource (lib "eagle-import") (part "PIN-1X6_6STM"))
    )
    (comp (ref "J8")
      (value "HDR 1x6 ST-M")
      (footprint "eagle-import:HDR_1X06")
      (fields (field (name "MPN") "77311-124-06LF") (field (name "MNF") "NP") (field (name "MPN_1") "NP"))
      (libsource (lib "eagle-import") (part "PIN-1X6_6STM"))
    )
    (comp (ref "J9")
      (value "HDR 1x2 ST-M")
      (footprint "eagle-import:HDR_1X2")
      (fields (field (name "MPN") "77311-124-02LF"))
      (libsource (lib "eagle-import") (part "PIN-1X2HDR2STMS"))
    )
    (comp (ref "L1")
      (value "10uH")
      (footprint "eagle-import:IND_5X5MM-5045")
      (fields (field (name "MPN") "VLS5045EX-100M"))
      (libsource (lib "eagle-import") (part "INDUCTOR"))
    )
    (comp (ref "M1")
      (value "7.5V 13.4A PS")
      (footprint "eagle-import:PS_5X3_MOLEX8P")
      (fields (field (name "MPN") "CFM100M075"))
      (libsource (lib "eagle-import") (part "PS_MOLEX8P"))
    )
    (comp (ref "R1")
      (value "56 kΩ")
      (footprint "eagle-import:R0603")
      (fields
        (field (name "MPN") "CRCW060356K0FKEA")
        (field (name "POWER") "0.1W")
        (field (name "TOLERANCE") "1%")
      )
      (libsource (lib "eagle-import") (part "RES_0603_56K0"))
    )
    (comp (ref "R2")
      (value "10 kΩ")
      (footprint "eagle-import:R0603")
      (fields
        (field (name "MPN") "CRCW060310K0FKEA")
        (field (name "POWER") "0.1W")
        (field (name "TOLERANCE") "1%")
      )
      (libsource (lib "eagle-import") (part "RES_0603_10K0"))
    )
    (comp (ref "R3")
      (value "100 Ω")
      (footprint "eagle-import:R0603")
      (fields
        (field (name "MPN") "CRCW0603100RFKEA")
        (field (name "POWER") "0.1W")
        (field (name "TOLERANCE") "1%")
      )
      (libsource (lib "eagle-import") (part "RES_0603_100R"))
    )
    (comp (ref "R4")
      (value "10 kΩ")
      (footprint "eagle-import:R0603")
      (fields
        (field (name "MPN") "CRCW060310K0FKEA")
        (field (name "POWER") "0.1W")
        (field (name "TOLERANCE") "1%")
      )
      (libsource (lib "eagle-import") (part "RES_0603_10K0"))
    )
    (comp (ref "R5")
      (value "100 Ω")
      (footprint "eagle-import:R0603")
      (fields
        (field (name "MPN") "CRCW0603100RFKEA")
        (field (name "POWER") "0.1W")
        (field (name "TOLERANCE") "1%")
      )
      (libsource (lib "eagle-import") (part "RES_0603_100R"))
    )
    (comp (ref "R6")
      (value "10 kΩ")
      (footprint "eagle-import:R0603")
      (fields
        (field (name "MPN") "CRCW060310K0FKEA")
        (field (name "POWER") "0.1W")
        (field (name "TOLERANCE") "1%")
      )
      (libsource (lib "eagle-import") (part "RES_0603_10K0"))
    )
    (comp (ref "R7")
      (value "100 Ω")
      (footprint "eagle-import:R0603")
      (fields
        (field (name "MPN") "CRCW0603100RFKEA")
        (field (name "POWER") "0.1W")
        (field (name "TOLERANCE") "1%")
      )
      (libsource (lib "eagle-import") (part "RES_0603_100R"))
    )
    (comp (ref "R8")
      (value "100 Ω")
      (footprint "eagle-import:R0603")
      (fields
        (field (name "MPN") "CRCW0603100RFKEA")
        (field (name "POWER") "0.1W")
        (field (name "TOLERANCE") "1%")
      )
      (libsource (lib "eagle-import") (part "RES_0603_100R"))
    )
    (comp (ref "R9")
      (value "0 Ω")
      (footprint "eagle-import:R0603")
      (fields (field (name "MPN") "CRCW06030000Z0EA"))
      (libsource (lib "eagle-import") (part "RES_0603_0000"))
    )
    (comp (ref "R10")
      (value "10 kΩ")
      (footprint "eagle-import:R0603")
      (fields
        (field (name "MPN") "CRCW060310K0FKEA")
        (field (name "POWER") "0.1W")
        (field (name "TOLERANCE") "1%")
      )
      (libsource (lib "eagle-import") (part "RES_0603_10K0"))
    )
    (comp (ref "R11")
      (value "10 kΩ")
      (footprint "eagle-import:R0603")
      (fields
        (field (name "MPN") "CRCW060310K0FKEA")
        (field (name "POWER") "0.1W")
        (field (name "TOLERANCE") "1%")
      )
      (libsource (lib "eagle-import") (part "RES_0603_10K0"))
    )
    (comp (ref "R12")
      (value "10 kΩ")
      (footprint "eagle-import:R0603")
      (fields
        (field (name "MPN") "CRCW060310K0FKEA")
        (field (name "POWER") "0.1W")
        (field (name "TOLERANCE") "1%")
      )
      (libsource (lib "eagle-import") (part "RES_0603_10K0"))
    )
    (comp (ref "R13")
      (value "0 Ω")
      (footprint "eagle-import:R0603")
      (fields (field (name "MPN") "CRCW06030000Z0EA"))
      (libsource (lib "eagle-import") (part "RES_0603_0000"))
    )
    (comp (ref "R14")
      (value "NP")
      (footprint "eagle-import:R0603")
      (libsource (lib "eagle-import") (part "RES_0603_NP"))
    )
    (comp (ref "S1")
      (value "SPST RA")
      (footprint "eagle-import:SITCH_PB_RA_800SP9B6M6RE")
      (fields (field (name "MPN") "800SP9B6M6RE"))
      (libsource (lib "eagle-import") (part "MOM_SWITCH_SPST_SH"))
    )
    (comp (ref "S2")
      (value "SPST RA")
      (footprint "eagle-import:SITCH_PB_RA_800SP9B6M6RE")
      (fields (field (name "MPN") "800SP9B6M6RE"))
      (libsource (lib "eagle-import") (part "MOM_SWITCH_SPST_SH"))
    )
    (comp (ref "S3")
      (value "DIP8-RA")
      (footprint "eagle-import:SWITCHX8_DIP_RA_0.1IN")
      (fields (field (name "MPN") "DS03-254-08BE") (field (name "VOLTAGE") "24V"))
      (libsource (lib "eagle-import") (part "SWITCH_X8_DIPSWDTS65"))
    )
    (comp (ref "U$1")
      (value "FIDUCIAL")
      (footprint "eagle-import:FIDUCIAL_1MM")
      (libsource (lib "eagle-import") (part "FIDUCIAL"))
    )
    (comp (ref "U$2")
      (value "FIDUCIAL")
      (footprint "eagle-import:FIDUCIAL_1MM")
      (libsource (lib "eagle-import") (part "FIDUCIAL"))
    )
    (comp (ref "U$3")
      (value "FIDUCIAL")
      (footprint "eagle-import:FIDUCIAL_1MM")
      (libsource (lib "eagle-import") (part "FIDUCIAL"))
    )
    (comp (ref "Y1")
      (value "24.0MHz")
      (footprint "eagle-import:XTAL4P_3.2X2.5MM")
      (fields (field (name "MPN") "ECS-240-8-33-RWY-TR"))
      (libsource (lib "eagle-import") (part "XTAL4P"))
    )
    (comp (ref "C201")
      (value "0.10uF")
      (footprint "eagle-import:MLCC_0603")
      (fields
        (field (name "MPN") "06035C104JAT2A")
        (field (name "TOLERANCE") "5%")
        (field (name "VOLTAGE") "50V")
      )
      (libsource (lib "eagle-import") (part "MLCC_0603_100N"))
    )
    (comp (ref "C202")
      (value "0.10uF")
      (footprint "eagle-import:MLCC_0603")
      (fields
        (field (name "MPN") "06035C104JAT2A")
        (field (name "TOLERANCE") "5%")
        (field (name "VOLTAGE") "50V")
      )
      (libsource (lib "eagle-import") (part "MLCC_0603_100N"))
    )
    (comp (ref "C203")
      (value "0.10uF")
      (footprint "eagle-import:MLCC_0603")
      (fields
        (field (name "MPN") "06035C104JAT2A")
        (field (name "TOLERANCE") "5%")
        (field (name "VOLTAGE") "50V")
      )
      (libsource (lib "eagle-import") (part "MLCC_0603_100N"))
    )
    (comp (ref "C204")
      (value "0.10uF")
      (footprint "eagle-import:MLCC_0603")
      (fields
        (field (name "MPN") "06035C104JAT2A")
        (field (name "TOLERANCE") "5%")
        (field (name "VOLTAGE") "50V")
      )
      (libsource (lib "eagle-import") (part "MLCC_0603_100N"))
    )
    (comp (ref "C205")
      (value "10uF")
      (footprint "eagle-import:MLCC_1206")
      (fields (field (name "VOLTAGE") "35V") (field (name "MPN") "GMK316AB7106KL-TR"))
      (libsource (lib "eagle-import") (part "MLCC1206_"))
    )
    (comp (ref "C206")
      (value "10uF")
      (footprint "eagle-import:MLCC_0603")
      (fields
        (field (name "MPN") "0603ZD106KAT2A")
        (field (name "TOLERANCE") "10%")
        (field (name "VOLTAGE") "10V")
      )
      (libsource (lib "eagle-import") (part "MLCC_0603_10UF-10V"))
    )
    (comp (ref "C207")
      (value "10uF")
      (footprint "eagle-import:MLCC_0603")
      (fields
        (field (name "MPN") "0603ZD106KAT2A")
        (field (name "TOLERANCE") "10%")
        (field (name "VOLTAGE") "10V")
      )
      (libsource (lib "eagle-import") (part "MLCC_0603_10UF-10V"))
    )
    (comp (ref "C208")
      (value "0.10uF")
      (footprint "eagle-import:MLCC_0603")
      (fields
        (field (name "MPN") "06035C104JAT2A")
        (field (name "TOLERANCE") "5%")
        (field (name "VOLTAGE") "50V")
      )
      (libsource (lib "eagle-import") (part "MLCC_0603_100N"))
    )
    (comp (ref "C209")
      (value "0.10uF")
      (footprint "eagle-import:MLCC_0603")
      (fields
        (field (name "MPN") "06035C104JAT2A")
        (field (name "TOLERANCE") "5%")
        (field (name "VOLTAGE") "50V")
      )
      (libsource (lib "eagle-import") (part "MLCC_0603_100N"))
    )
    (comp (ref "IC201")
      (value "TLV2197")
      (footprint "eagle-import:VSSOP8-DGK-065P")
      (fields (field (name "MPN") "TLV2197QDGKRQ1"))
      (libsource (lib "eagle-import") (part "OPA_D_TLV2172IDGKRTLV2197QDGK"))
    )
    (comp (ref "IC202")
      (value "TC7WZ08")
      (footprint "eagle-import:SOP50P310X90-8N")
      (fields (field (name "MPN") "TC7WZ08FK"))
      (libsource (lib "eagle-import") (part "AND2_TSOP8"))
    )
    (comp (ref "IC203")
      (value "TC7WZ08")
      (footprint "eagle-import:SOP50P310X90-8N")
      (fields (field (name "MPN") "TC7WZ08FK"))
      (libsource (lib "eagle-import") (part "AND2_TSOP8"))
    )
    (comp (ref "IC204")
      (value "TLV2197")
      (footprint "eagle-import:VSSOP8-DGK-065P")
      (fields (field (name "MPN") "TLV2197QDGKRQ1"))
      (libsource (lib "eagle-import") (part "OPA_D_TLV2172IDGKRTLV2197QDGK"))
    )
    (comp (ref "IC205")
      (value "TLV2197")
      (footprint "eagle-import:VSSOP8-DGK-065P")
      (fields (field (name "MPN") "TLV2197QDGKRQ1"))
      (libsource (lib "eagle-import") (part "OPA_D_TLV2172IDGKRTLV2197QDGK"))
    )
    (comp (ref "J201")
      (value "RA BNC 50 Ohm")
      (footprint "eagle-import:BNC_AMP_227161")
      (fields (field (name "MPN") "5227161-6"))
      (libsource (lib "eagle-import") (part "BNC-4P"))
    )
    (comp (ref "J202")
      (value "RA BNC 50 Ohm")
      (footprint "eagle-import:BNC_AMP_227161")
      (fields (field (name "MPN") "5227161-6"))
      (libsource (lib "eagle-import") (part "BNC-4P"))
    )
    (comp (ref "J203")
      (value "4P Thor LED RA")
      (footprint "eagle-import:CIR_PHX4P_RA")
      (fields (field (name "MPN") "1526169"))
      (libsource (lib "eagle-import") (part "CIRCULAR-4P-THOR-F"))
    )
    (comp (ref "J204")
      (value "4P Thor LED RA")
      (footprint "eagle-import:CIR_PHX4P_RA")
      (fields (field (name "MPN") "1526169"))
      (libsource (lib "eagle-import") (part "CIRCULAR-4P-THOR-F"))
    )
    (comp (ref "Q201")
      (value "DMG6601")
      (footprint "eagle-import:SOT95P280X100-6N")
      (fields (field (name "MPN") "DMG6601LVT-7"))
      (libsource (lib "eagle-import") (part "MOSFET-PN"))
    )
    (comp (ref "Q202")
      (value "DMG6601")
      (footprint "eagle-import:SOT95P280X100-6N")
      (fields (field (name "MPN") "DMG6601LVT-7"))
      (libsource (lib "eagle-import") (part "MOSFET-PN"))
    )
    (comp (ref "Q203")
      (value "BSC12DN20N")
      (footprint "eagle-import:TDSON-8")
      (fields (field (name "MPN") "BSC12DN20NS3 G") (field (name "POWER") "50W"))
      (libsource (lib "eagle-import") (part "MOSFET-NN-MOSFETBSC12DN20NS3G"))
    )
    (comp (ref "Q204")
      (value "BSC12DN20N")
      (footprint "eagle-import:TDSON-8")
      (fields (field (name "MPN") "BSC12DN20NS3 G") (field (name "POWER") "50W"))
      (libsource (lib "eagle-import") (part "MOSFET-NN-MOSFETBSC12DN20NS3G"))
    )
    (comp (ref "R201")
      (value "10 kΩ")
      (footprint "eagle-import:R0603")
      (fields
        (field (name "MPN") "CRCW060310K0FKEA")
        (field (name "POWER") "0.1W")
        (field (name "TOLERANCE") "1%")
      )
      (libsource (lib "eagle-import") (part "RES_0603_10K0"))
    )
    (comp (ref "R202")
      (value "10 kΩ")
      (footprint "eagle-import:R0603")
      (fields
        (field (name "MPN") "CRCW060310K0FKEA")
        (field (name "POWER") "0.1W")
        (field (name "TOLERANCE") "1%")
      )
      (libsource (lib "eagle-import") (part "RES_0603_10K0"))
    )
    (comp (ref "R203")
      (value "4.3 kΩ")
      (footprint "eagle-import:R0603")
      (fields
        (field (name "MPN") "CRCW06034K30FKEA")
        (field (name "POWER") "0.1W")
        (field (name "TOLERANCE") "1%")
      )
      (libsource (lib "eagle-import") (part "RES_0603_4K30"))
    )
    (comp (ref "R204")
      (value "4.3 kΩ")
      (footprint "eagle-import:R0603")
      (fields
        (field (name "MPN") "CRCW06034K30FKEA")
        (field (name "POWER") "0.1W")
        (field (name "TOLERANCE") "1%")
      )
      (libsource (lib "eagle-import") (part "RES_0603_4K30"))
    )
    (comp (ref "R205")
      (value "33 Ω")
      (footprint "eagle-import:R0603")
      (fields
        (field (name "MPN") "CRCW060333R0FKEA")
        (field (name "POWER") "0.1W")
        (field (name "TOLERANCE") "1%")
      )
      (libsource (lib "eagle-import") (part "RES_0603_33R0"))
    )
    (comp (ref "R206")
      (value "33 Ω")
      (footprint "eagle-import:R0603")
      (fields
        (field (name "MPN") "CRCW060333R0FKEA")
        (field (name "POWER") "0.1W")
        (field (name "TOLERANCE") "1%")
      )
      (libsource (lib "eagle-import") (part "RES_0603_33R0"))
    )
    (comp (ref "R207")
      (value "3.3 kΩ")
      (footprint "eagle-import:R0603")
      (fields
        (field (name "MPN") "CRCW06033K30FKEA")
        (field (name "POWER") "0.1W")
        (field (name "TOLERANCE") "1%")
      )
      (libsource (lib "eagle-import") (part "RES_0603_3K30"))
    )
    (comp (ref "R208")
      (value "3.3 kΩ")
      (footprint "eagle-import:R0603")
      (fields
        (field (name "MPN") "CRCW06033K30FKEA")
        (field (name "POWER") "0.1W")
        (field (name "TOLERANCE") "1%")
      )
      (libsource (lib "eagle-import") (part "RES_0603_3K30"))
    )
    (comp (ref "R209")
      (value "5K")
      (footprint "eagle-import:MTBOURNS_RA_LONG")
      (fields (field (name "MPN") "3006P-7-502LF"))
      (libsource (lib "eagle-import") (part "RES_TRIM_5K_RA_MTURN"))
    )
    (comp (ref "R210")
      (value "5K")
      (footprint "eagle-import:MTBOURNS_RA_LONG")
      (fields (field (name "MPN") "3006P-7-502LF"))
      (libsource (lib "eagle-import") (part "RES_TRIM_5K_RA_MTURN"))
    )
    (comp (ref "R211")
      (value "10 kΩ")
      (footprint "eagle-import:R0603")
      (fields
        (field (name "MPN") "CRCW060310K0FKEA")
        (field (name "POWER") "0.1W")
        (field (name "TOLERANCE") "1%")
      )
      (libsource (lib "eagle-import") (part "RES_0603_10K0"))
    )
    (comp (ref "R212")
      (value "10 kΩ")
      (footprint "eagle-import:R0603")
      (fields
        (field (name "MPN") "CRCW060310K0FKEA")
        (field (name "POWER") "0.1W")
        (field (name "TOLERANCE") "1%")
      )
      (libsource (lib "eagle-import") (part "RES_0603_10K0"))
    )
    (comp (ref "R213")
      (value "0 Ω")
      (footprint "eagle-import:R0603")
      (fields (field (name "MPN") "CRCW06030000Z0EA"))
      (libsource (lib "eagle-import") (part "RES_0603_0000"))
    )
    (comp (ref "R214")
      (value "33 Ω")
      (footprint "eagle-import:R0603")
      (fields
        (field (name "MPN") "CRCW060333R0FKEA")
        (field (name "POWER") "0.1W")
        (field (name "TOLERANCE") "1%")
      )
      (libsource (lib "eagle-import") (part "RES_0603_33R0"))
    )
    (comp (ref "R215")
      (value "33 Ω")
      (footprint "eagle-import:R0603")
      (fields
        (field (name "MPN") "CRCW060333R0FKEA")
        (field (name "POWER") "0.1W")
        (field (name "TOLERANCE") "1%")
      )
      (libsource (lib "eagle-import") (part "RES_0603_33R0"))
    )
    (comp (ref "R216")
      (value "1 Ohm")
      (footprint "eagle-import:R1225")
      (fields (field (name "MPN") "WK73S3A3TTE1R00F"))
      (libsource (lib "eagle-import") (part "RES_1225_"))
    )
    (comp (ref "R217")
      (value "1 Ohm")
      (footprint "eagle-import:R1225")
      (fields (field (name "MPN") "WK73S3A3TTE1R00F"))
      (libsource (lib "eagle-import") (part "RES_1225_"))
    )
    (comp (ref "C401")
      (value "0.10uF")
      (footprint "eagle-import:MLCC_0603")
      (fields
        (field (name "MPN") "06035C104JAT2A")
        (field (name "TOLERANCE") "5%")
        (field (name "VOLTAGE") "50V")
      )
      (libsource (lib "eagle-import") (part "MLCC_0603_100N"))
    )
    (comp (ref "C402")
      (value "0.10uF")
      (footprint "eagle-import:MLCC_0603")
      (fields
        (field (name "MPN") "06035C104JAT2A")
        (field (name "TOLERANCE") "5%")
        (field (name "VOLTAGE") "50V")
      )
      (libsource (lib "eagle-import") (part "MLCC_0603_100N"))
    )
    (comp (ref "C403")
      (value "0.10uF")
      (footprint "eagle-import:MLCC_0603")
      (fields
        (field (name "MPN") "06035C104JAT2A")
        (field (name "TOLERANCE") "5%")
        (field (name "VOLTAGE") "50V")
      )
      (libsource (lib "eagle-import") (part "MLCC_0603_100N"))
    )
    (comp (ref "C404")
      (value "0.10uF")
      (footprint "eagle-import:MLCC_0603")
      (fields
        (field (name "MPN") "06035C104JAT2A")
        (field (name "TOLERANCE") "5%")
        (field (name "VOLTAGE") "50V")
      )
      (libsource (lib "eagle-import") (part "MLCC_0603_100N"))
    )
    (comp (ref "C405")
      (value "10uF")
      (footprint "eagle-import:MLCC_1206")
      (fields (field (name "VOLTAGE") "35V") (field (name "MPN") "GMK316AB7106KL-TR"))
      (libsource (lib "eagle-import") (part "MLCC1206_"))
    )
    (comp (ref "C406")
      (value "10uF")
      (footprint "eagle-import:MLCC_0603")
      (fields
        (field (name "MPN") "0603ZD106KAT2A")
        (field (name "TOLERANCE") "10%")
        (field (name "VOLTAGE") "10V")
      )
      (libsource (lib "eagle-import") (part "MLCC_0603_10UF-10V"))
    )
    (comp (ref "C407")
      (value "10uF")
      (footprint "eagle-import:MLCC_0603")
      (fields
        (field (name "MPN") "0603ZD106KAT2A")
        (field (name "TOLERANCE") "10%")
        (field (name "VOLTAGE") "10V")
      )
      (libsource (lib "eagle-import") (part "MLCC_0603_10UF-10V"))
    )
    (comp (ref "C408")
      (value "0.10uF")
      (footprint "eagle-import:MLCC_0603")
      (fields
        (field (name "MPN") "06035C104JAT2A")
        (field (name "TOLERANCE") "5%")
        (field (name "VOLTAGE") "50V")
      )
      (libsource (lib "eagle-import") (part "MLCC_0603_100N"))
    )
    (comp (ref "C409")
      (value "0.10uF")
      (footprint "eagle-import:MLCC_0603")
      (fields
        (field (name "MPN") "06035C104JAT2A")
        (field (name "TOLERANCE") "5%")
        (field (name "VOLTAGE") "50V")
      )
      (libsource (lib "eagle-import") (part "MLCC_0603_100N"))
    )
    (comp (ref "IC401")
      (value "TLV2197")
      (footprint "eagle-import:VSSOP8-DGK-065P")
      (fields (field (name "MPN") "TLV2197QDGKRQ1"))
      (libsource (lib "eagle-import") (part "OPA_D_TLV2172IDGKRTLV2197QDGK"))
    )
    (comp (ref "IC402")
      (value "TC7WZ08")
      (footprint "eagle-import:SOP50P310X90-8N")
      (fields (field (name "MPN") "TC7WZ08FK"))
      (libsource (lib "eagle-import") (part "AND2_TSOP8"))
    )
    (comp (ref "IC403")
      (value "TC7WZ08")
      (footprint "eagle-import:SOP50P310X90-8N")
      (fields (field (name "MPN") "TC7WZ08FK"))
      (libsource (lib "eagle-import") (part "AND2_TSOP8"))
    )
    (comp (ref "IC404")
      (value "TLV2197")
      (footprint "eagle-import:VSSOP8-DGK-065P")
      (fields (field (name "MPN") "TLV2197QDGKRQ1"))
      (libsource (lib "eagle-import") (part "OPA_D_TLV2172IDGKRTLV2197QDGK"))
    )
    (comp (ref "IC405")
      (value "TLV2197")
      (footprint "eagle-import:VSSOP8-DGK-065P")
      (fields (field (name "MPN") "TLV2197QDGKRQ1"))
      (libsource (lib "eagle-import") (part "OPA_D_TLV2172IDGKRTLV2197QDGK"))
    )
    (comp (ref "J401")
      (value "RA BNC 50 Ohm")
      (footprint "eagle-import:BNC_AMP_227161")
      (fields (field (name "MPN") "5227161-6"))
      (libsource (lib "eagle-import") (part "BNC-4P"))
    )
    (comp (ref "J402")
      (value "RA BNC 50 Ohm")
      (footprint "eagle-import:BNC_AMP_227161")
      (fields (field (name "MPN") "5227161-6"))
      (libsource (lib "eagle-import") (part "BNC-4P"))
    )
    (comp (ref "J403")
      (value "4P Thor LED RA")
      (footprint "eagle-import:CIR_PHX4P_RA")
      (fields (field (name "MPN") "1526169"))
      (libsource (lib "eagle-import") (part "CIRCULAR-4P-THOR-F"))
    )
    (comp (ref "J404")
      (value "4P Thor LED RA")
      (footprint "eagle-import:CIR_PHX4P_RA")
      (fields (field (name "MPN") "1526169"))
      (libsource (lib "eagle-import") (part "CIRCULAR-4P-THOR-F"))
    )
    (comp (ref "Q401")
      (value "DMG6601")
      (footprint "eagle-import:SOT95P280X100-6N")
      (fields (field (name "MPN") "DMG6601LVT-7"))
      (libsource (lib "eagle-import") (part "MOSFET-PN"))
    )
    (comp (ref "Q402")
      (value "DMG6601")
      (footprint "eagle-import:SOT95P280X100-6N")
      (fields (field (name "MPN") "DMG6601LVT-7"))
      (libsource (lib "eagle-import") (part "MOSFET-PN"))
    )
    (comp (ref "Q403")
      (value "BSC12DN20N")
      (footprint "eagle-import:TDSON-8")
      (fields (field (name "MPN") "BSC12DN20NS3 G") (field (name "POWER") "50W"))
      (libsource (lib "eagle-import") (part "MOSFET-NN-MOSFETBSC12DN20NS3G"))
    )
    (comp (ref "Q404")
      (value "BSC12DN20N")
      (footprint "eagle-import:TDSON-8")
      (fields (field (name "MPN") "BSC12DN20NS3 G") (field (name "POWER") "50W"))
      (libsource (lib "eagle-import") (part "MOSFET-NN-MOSFETBSC12DN20NS3G"))
    )
    (comp (ref "R401")
      (value "10 kΩ")
      (footprint "eagle-import:R0603")
      (fields
        (field (name "MPN") "CRCW060310K0FKEA")
        (field (name "POWER") "0.1W")
        (field (name "TOLERANCE") "1%")
      )
      (libsource (lib "eagle-import") (part "RES_0603_10K0"))
    )
    (comp (ref "R402")
      (value "10 kΩ")
      (footprint "eagle-import:R0603")
      (fields
        (field (name "MPN") "CRCW060310K0FKEA")
        (field (name "POWER") "0.1W")
        (field (name "TOLERANCE") "1%")
      )
      (libsource (lib "eagle-import") (part "RES_0603_10K0"))
    )
    (comp (ref "R403")
      (value "4.3 kΩ")
      (footprint "eagle-import:R0603")
      (fields
        (field (name "MPN") "CRCW06034K30FKEA")
        (field (name "POWER") "0.1W")
        (field (name "TOLERANCE") "1%")
      )
      (libsource (lib "eagle-import") (part "RES_0603_4K30"))
    )
    (comp (ref "R404")
      (value "4.3 kΩ")
      (footprint "eagle-import:R0603")
      (fields
        (field (name "MPN") "CRCW06034K30FKEA")
        (field (name "POWER") "0.1W")
        (field (name "TOLERANCE") "1%")
      )
      (libsource (lib "eagle-import") (part "RES_0603_4K30"))
    )
    (comp (ref "R405")
      (value "33 Ω")
      (footprint "eagle-import:R0603")
      (fields
        (field (name "MPN") "CRCW060333R0FKEA")
        (field (name "POWER") "0.1W")
        (field (name "TOLERANCE") "1%")
      )
      (libsource (lib "eagle-import") (part "RES_0603_33R0"))
    )
    (comp (ref "R406")
      (value "33 Ω")
      (footprint "eagle-import:R0603")
      (fields
        (field (name "MPN") "CRCW060333R0FKEA")
        (field (name "POWER") "0.1W")
        (field (name "TOLERANCE") "1%")
      )
      (libsource (lib "eagle-import") (part "RES_0603_33R0"))
    )
    (comp (ref "R407")
      (value "3.3 kΩ")
      (footprint "eagle-import:R0603")
      (fields
        (field (name "MPN") "CRCW06033K30FKEA")
        (field (name "POWER") "0.1W")
        (field (name "TOLERANCE") "1%")
      )
      (libsource (lib "eagle-import") (part "RES_0603_3K30"))
    )
    (comp (ref "R408")
      (value "3.3 kΩ")
      (footprint "eagle-import:R0603")
      (fields
        (field (name "MPN") "CRCW06033K30FKEA")
        (field (name "POWER") "0.1W")
        (field (name "TOLERANCE") "1%")
      )
      (libsource (lib "eagle-import") (part "RES_0603_3K30"))
    )
    (comp (ref "R409")
      (value "5K")
      (footprint "eagle-import:MTBOURNS_RA_LONG")
      (fields (field (name "MPN") "3006P-7-502LF"))
      (libsource (lib "eagle-import") (part "RES_TRIM_5K_RA_MTURN"))
    )
    (comp (ref "R410")
      (value "5K")
      (footprint "eagle-import:MTBOURNS_RA_LONG")
      (fields (field (name "MPN") "3006P-7-502LF"))
      (libsource (lib "eagle-import") (part "RES_TRIM_5K_RA_MTURN"))
    )
    (comp (ref "R411")
      (value "10 kΩ")
      (footprint "eagle-import:R0603")
      (fields
        (field (name "MPN") "CRCW060310K0FKEA")
        (field (name "POWER") "0.1W")
        (field (name "TOLERANCE") "1%")
      )
      (libsource (lib "eagle-import") (part "RES_0603_10K0"))
    )
    (comp (ref "R412")
      (value "10 kΩ")
      (footprint "eagle-import:R0603")
      (fields
        (field (name "MPN") "CRCW060310K0FKEA")
        (field (name "POWER") "0.1W")
        (field (name "TOLERANCE") "1%")
      )
      (libsource (lib "eagle-import") (part "RES_0603_10K0"))
    )
    (comp (ref "R413")
      (value "0 Ω")
      (footprint "eagle-import:R0603")
      (fields (field (name "MPN") "CRCW06030000Z0EA"))
      (libsource (lib "eagle-import") (part "RES_0603_0000"))
    )
    (comp (ref "R414")
      (value "33 Ω")
      (footprint "eagle-import:R0603")
      (fields
        (field (name "MPN") "CRCW060333R0FKEA")
        (field (name "POWER") "0.1W")
        (field (name "TOLERANCE") "1%")
      )
      (libsource (lib "eagle-import") (part "RES_0603_33R0"))
    )
    (comp (ref "R415")
      (value "33 Ω")
      (footprint "eagle-import:R0603")
      (fields
        (field (name "MPN") "CRCW060333R0FKEA")
        (field (name "POWER") "0.1W")
        (field (name "TOLERANCE") "1%")
      )
      (libsource (lib "eagle-import") (part "RES_0603_33R0"))
    )
    (comp (ref "R416")
      (value "1 Ohm")
      (footprint "eagle-import:R1225")
      (fields (field (name "MPN") "WK73S3A3TTE1R00F"))
      (libsource (lib "eagle-import") (part "RES_1225_"))
    )
    (comp (ref "R417")
      (value "1 Ohm")
      (footprint "eagle-import:R1225")
      (fields (field (name "MPN") "WK73S3A3TTE1R00F"))
      (libsource (lib "eagle-import") (part "RES_1225_"))
    )
  )
  (nets
    (net (code "1") (name "+3.3V") (class "Default")
      (node (ref "C1") (pin "2") (pinfunction "2_2") (pintype "bidirectional"))
      (node (ref "C108") (pin "2") (pinfunction "2_2") (pintype "bidirectional"))
      (node (ref "C109") (pin "2") (pinfunction "2_2") (pintype "bidirectional"))
      (node (ref "C12") (pin "2") (pinfunction "2_2") (pintype "bidirectional"))
      (node (ref "C13") (pin "2") (pinfunction "2_2") (pintype "bidirectional"))
      (node (ref "C2") (pin "2") (pinfunction "2_2") (pintype "bidirectional"))
      (node (ref "C208") (pin "2") (pinfunction "2_2") (pintype "bidirectional"))
      (node (ref "C209") (pin "2") (pinfunction "2_2") (pintype "bidirectional"))
      (node (ref "C308") (pin "2") (pinfunction "2_2") (pintype "bidirectional"))
      (node (ref "C309") (pin "2") (pinfunction "2_2") (pintype "bidirectional"))
      (node (ref "C408") (pin "2") (pinfunction "2_2") (pintype "bidirectional"))
      (node (ref "C409") (pin "2") (pinfunction "2_2") (pintype "bidirectional"))
      (node (ref "C6") (pin "1") (pinfunction "1_1") (pintype "bidirectional"))
      (node (ref "D2") (pin "2") (pinfunction "A_2") (pintype "bidirectional"))
      (node (ref "IC102") (pin "8") (pinfunction "VCC_8") (pintype "power_in"))
      (node (ref "IC103") (pin "8") (pinfunction "VCC_8") (pintype "power_in"))
      (node (ref "IC2") (pin "1") (pinfunction "VO_1") (pintype "bidirectional"))
      (node (ref "IC2") (pin "2") (pinfunction "FB_2") (pintype "bidirectional"))
      (node (ref "IC202") (pin "8") (pinfunction "VCC_8") (pintype "power_in"))
      (node (ref "IC203") (pin "8") (pinfunction "VCC_8") (pintype "power_in"))
      (node (ref "IC3") (pin "8") (pinfunction "VCC_8") (pintype "power_in"))
      (node (ref "IC302") (pin "8") (pinfunction "VCC_8") (pintype "power_in"))
      (node (ref "IC303") (pin "8") (pinfunction "VCC_8") (pintype "power_in"))
      (node (ref "IC4") (pin "1") (pinfunction "VBAT_1") (pintype "bidirectional"))
      (node (ref "IC4") (pin "24") (pinfunction "VDD_1_24") (pintype "bidirectional"))
      (node (ref "IC4") (pin "36") (pinfunction "VDD_2_36") (pintype "bidirectional"))
      (node (ref "IC4") (pin "48") (pinfunction "VDD_3_48") (pintype "bidirectional"))
      (node (ref "IC402") (pin "8") (pinfunction "VCC_8") (pintype "power_in"))
      (node (ref "IC403") (pin "8") (pinfunction "VCC_8") (pintype "power_in"))
      (node (ref "IC5") (pin "8") (pinfunction "VCC_8") (pintype "power_in"))
      (node (ref "J2") (pin "2") (pinfunction "2_2") (pintype "passive"))
      (node (ref "J6") (pin "6") (pinfunction "6_6") (pintype "passive"))
      (node (ref "Q101") (pin "2") (pinfunction "S_2") (pintype "passive"))
      (node (ref "Q102") (pin "2") (pinfunction "S_2") (pintype "passive"))
      (node (ref "Q201") (pin "2") (pinfunction "S_2") (pintype "passive"))
      (node (ref "Q202") (pin "2") (pinfunction "S_2") (pintype "passive"))
      (node (ref "Q301") (pin "2") (pinfunction "S_2") (pintype "passive"))
      (node (ref "Q302") (pin "2") (pinfunction "S_2") (pintype "passive"))
      (node (ref "Q401") (pin "2") (pinfunction "S_2") (pintype "passive"))
      (node (ref "Q402") (pin "2") (pinfunction "S_2") (pintype "passive"))
      (node (ref "R4") (pin "2") (pinfunction "2_2") (pintype "passive"))
      (node (ref "R6") (pin "2") (pinfunction "2_2") (pintype "passive"))
      (node (ref "R9") (pin "2") (pinfunction "2_2") (pintype "passive"))
      (node (ref "S3") (pin "8") (pinfunction "P$2_8") (pintype "passive"))
    )
    (net (code "2") (name "+5V") (class "Default")
      (node (ref "C10") (pin "2") (pinfunction "2_2") (pintype "bidirectional"))
      (node (ref "C101") (pin "2") (pinfunction "2_2") (pintype "bidirectional"))
      (node (ref "C102") (pin "2") (pinfunction "2_2") (pintype "bidirectional"))
      (node (ref "C103") (pin "2") (pinfunction "2_2") (pintype "bidirectional"))
      (node (ref "C106") (pin "2") (pinfunction "2_2") (pintype "bidirectional"))
      (node (ref "C107") (pin "2") (pinfunction "2_2") (pintype "bidirectional"))
      (node (ref "C11") (pin "2") (pinfunction "2_2") (pintype "bidirectional"))
      (node (ref "C201") (pin "2") (pinfunction "2_2") (pintype "bidirectional"))
      (node (ref "C202") (pin "2") (pinfunction "2_2") (pintype "bidirectional"))
      (node (ref "C203") (pin "2") (pinfunction "2_2") (pintype "bidirectional"))
      (node (ref "C206") (pin "2") (pinfunction "2_2") (pintype "bidirectional"))
      (node (ref "C207") (pin "2") (pinfunction "2_2") (pintype "bidirectional"))
      (node (ref "C301") (pin "2") (pinfunction "2_2") (pintype "bidirectional"))
      (node (ref "C302") (pin "2") (pinfunction "2_2") (pintype "bidirectional"))
      (node (ref "C303") (pin "2") (pinfunction "2_2") (pintype "bidirectional"))
      (node (ref "C306") (pin "2") (pinfunction "2_2") (pintype "bidirectional"))
      (node (ref "C307") (pin "2") (pinfunction "2_2") (pintype "bidirectional"))
      (node (ref "C401") (pin "2") (pinfunction "2_2") (pintype "bidirectional"))
      (node (ref "C402") (pin "2") (pinfunction "2_2") (pintype "bidirectional"))
      (node (ref "C403") (pin "2") (pinfunction "2_2") (pintype "bidirectional"))
      (node (ref "C406") (pin "2") (pinfunction "2_2") (pintype "bidirectional"))
      (node (ref "C407") (pin "2") (pinfunction "2_2") (pintype "bidirectional"))
      (node (ref "C5") (pin "1") (pinfunction "1_1") (pintype "bidirectional"))
      (node (ref "C7") (pin "2") (pinfunction "2_2") (pintype "bidirectional"))
      (node (ref "C8") (pin "2") (pinfunction "2_2") (pintype "bidirectional"))
      (node (ref "C9") (pin "2") (pinfunction "2_2") (pintype "bidirectional"))
      (node (ref "IC101") (pin "8") (pinfunction "V+_8") (pintype "power_in"))
      (node (ref "IC104") (pin "8") (pinfunction "V+_8") (pintype "power_in"))
      (node (ref "IC2") (pin "5") (pinfunction "EN_5") (pintype "bidirectional"))
      (node (ref "IC2") (pin "8") (pinfunction "VCC_8") (pintype "bidirectional"))
      (node (ref "IC201") (pin "8") (pinfunction "V+_8") (pintype "power_in"))
      (node (ref "IC204") (pin "8") (pinfunction "V+_8") (pintype "power_in"))
      (node (ref "IC301") (pin "8") (pinfunction "V+_8") (pintype "power_in"))
      (node (ref "IC304") (pin "8") (pinfunction "V+_8") (pintype "power_in"))
      (node (ref "IC401") (pin "8") (pinfunction "V+_8") (pintype "power_in"))
      (node (ref "IC404") (pin "8") (pinfunction "V+_8") (pintype "power_in"))
      (node (ref "J2") (pin "9") (pinfunction "9_9") (pintype "passive"))
      (node (ref "J7") (pin "5") (pinfunction "5_5") (pintype "passive"))
      (node (ref "J9") (pin "2") (pinfunction "2_2") (pintype "passive"))
      (node (ref "L1") (pin "2") (pinfunction "2_2") (pintype "bidirectional"))
      (node (ref "R1") (pin "2") (pinfunction "2_2") (pintype "passive"))
      (node (ref "R111") (pin "2") (pinfunction "2_2") (pintype "passive"))
      (node (ref "R112") (pin "2") (pinfunction "2_2") (pintype "passive"))
      (node (ref "R113") (pin "2") (pinfunction "2_2") (pintype "passive"))
      (node (ref "R211") (pin "2") (pinfunction "2_2") (pintype "passive"))
      (node (ref "R212") (pin "2") (pinfunction "2_2") (pintype "passive"))
      (node (ref "R213") (pin "2") (pinfunction "2_2") (pintype "passive"))
      (node (ref "R311") (pin "2") (pinfunction "2_2") (pintype "passive"))
      (node (ref "R312") (pin "2") (pinfunction "2_2") (pintype "passive"))
      (node (ref "R313") (pin "2") (pinfunction "2_2") (pintype "passive"))
      (node (ref "R411") (pin "2") (pinfunction "2_2") (pintype "passive"))
      (node (ref "R412") (pin "2") (pinfunction "2_2") (pintype "passive"))
      (node (ref "R413") (pin "2") (pinfunction "2_2") (pintype "passive"))
    )
    (net (code "3") (name "+VPWR") (class "Default")
      (node (ref "C104") (pin "2") (pinfunction "2_2") (pintype "bidirectional"))
      (node (ref "C105") (pin "1") (pinfunction "1_1") (pintype "bidirectional"))
      (node (ref "C204") (pin "2") (pinfunction "2_2") (pintype "bidirectional"))
      (node (ref "C205") (pin "1") (pinfunction "1_1") (pintype "bidirectional"))
      (node (ref "C304") (pin "2") (pinfunction "2_2") (pintype "bidirectional"))
      (node (ref "C305") (pin "1") (pinfunction "1_1") (pintype "bidirectional"))
      (node (ref "C404") (pin "2") (pinfunction "2_2") (pintype "bidirectional"))
      (node (ref "C405") (pin "1") (pinfunction "1_1") (pintype "bidirectional"))
      (node (ref "J103") (pin "1") (pinfunction "1_1") (pintype "passive"))
      (node (ref "J104") (pin "1") (pinfunction "1_1") (pintype "passive"))
      (node (ref "J203") (pin "1") (pinfunction "1_1") (pintype "passive"))
      (node (ref "J204") (pin "1") (pinfunction "1_1") (pintype "passive"))
      (node (ref "J303") (pin "1") (pinfunction "1_1") (pintype "passive"))
      (node (ref "J304") (pin "1") (pinfunction "1_1") (pintype "passive"))
      (node (ref "J403") (pin "1") (pinfunction "1_1") (pintype "passive"))
      (node (ref "J404") (pin "1") (pinfunction "1_1") (pintype "passive"))
      (node (ref "M1") (pin "5") (pinfunction "V+1_5") (pintype "power_in"))
      (node (ref "M1") (pin "6") (pinfunction "V+2_6") (pintype "power_in"))
      (node (ref "M1") (pin "7") (pinfunction "V+3_7") (pintype "power_in"))
    )
    (net (code "4") (name "C1") (class "Default")
      (node (ref "IC104") (pin "1") (pinfunction "OUT_1") (pintype "output"))
      (node (ref "IC104") (pin "2") (pinfunction "-IN_2") (pintype "input"))
      (node (ref "IC4") (pin "10") (pinfunction "UART2_CTS/A0/PA0_10") (pintype "bidirectional"))
      (node (ref "J8") (pin "1") (pinfunction "1_1") (pintype "passive"))
    )
    (net (code "5") (name "C2") (class "Default")
      (node (ref "IC104") (pin "6") (pinfunction "-IN_6") (pintype "input"))
      (node (ref "IC104") (pin "7") (pinfunction "OUT_7") (pintype "output"))
      (node (ref "IC4") (pin "11") (pinfunction "UART2_RTS/A1/PA1_11") (pintype "bidirectional"))
      (node (ref "J8") (pin "2") (pinfunction "2_2") (pintype "passive"))
    )
    (net (code "6") (name "C3") (class "Default")
      (node (ref "IC204") (pin "1") (pinfunction "OUT_1") (pintype "output"))
      (node (ref "IC204") (pin "2") (pinfunction "-IN_2") (pintype "input"))
      (node (ref "IC4") (pin "12") (pinfunction "UART2_TX/A2/PA2_12") (pintype "bidirectional"))
      (node (ref "J8") (pin "3") (pinfunction "3_3") (pintype "passive"))
    )
    (net (code "7") (name "C4") (class "Default")
      (node (ref "IC204") (pin "6") (pinfunction "-IN_6") (pintype "input"))
      (node (ref "IC204") (pin "7") (pinfunction "OUT_7") (pintype "output"))
      (node (ref "IC4") (pin "13") (pinfunction "UART2_RX/A3/PA3_13") (pintype "bidirectional"))
      (node (ref "J8") (pin "4") (pinfunction "4_4") (pintype "passive"))
    )
    (net (code "8") (name "C5") (class "Default")
      (node (ref "IC304") (pin "1") (pinfunction "OUT_1") (pintype "output"))
      (node (ref "IC304") (pin "2") (pinfunction "-IN_2") (pintype "input"))
      (node (ref "IC4") (pin "14") (pinfunction "SP1_CS/A4/PA4_14") (pintype "bidirectional"))
      (node (ref "J8") (pin "5") (pinfunction "5_5") (pintype "passive"))
    )
    (net (code "9") (name "C6") (class "Default")
      (node (ref "IC304") (pin "6") (pinfunction "-IN_6") (pintype "input"))
      (node (ref "IC304") (pin "7") (pinfunction "OUT_7") (pintype "output"))
      (node (ref "IC4") (pin "15") (pinfunction "SP1_CLK/DAC/A5/PA5_15") (pintype "bidirectional"))
      (node (ref "J8") (pin "6") (pinfunction "6_6") (pintype "passive"))
    )
    (net (code "10") (name "C7") (class "Default")
      (node (ref "IC4") (pin "16") (pinfunction "SPI1_MISO/A6/PA6_16") (pintype "bidirectional"))
      (node (ref "IC404") (pin "1") (pinfunction "OUT_1") (pintype "output"))
      (node (ref "IC404") (pin "2") (pinfunction "-IN_2") (pintype "input"))
      (node (ref "J7") (pin "1") (pinfunction "1_1") (pintype "passive"))
    )
    (net (code "11") (name "C8") (class "Default")
      (node (ref "IC4") (pin "17") (pinfunction "SPI1_MOSI/A7/PA7_17") (pintype "bidirectional"))
      (node (ref "IC404") (pin "6") (pinfunction "-IN_6") (pintype "input"))
      (node (ref "IC404") (pin "7") (pinfunction "OUT_7") (pintype "output"))
      (node (ref "J7") (pin "2") (pinfunction "2_2") (pintype "passive"))
    )
    (net (code "12") (name "DIN") (class "Default")
      (node (ref "DS1") (pin "8") (pinfunction "DB1_8") (pintype "bidirectional"))
      (node (ref "IC4") (pin "28") (pinfunction "I2C4_SCL/SPI2_MOSI/PB15_28") (pintype "bidirectional"))
    )
    (net (code "13") (name "D{slash}~{C}") (class "Default")
      (node (ref "DS1") (pin "4") (pinfunction "D/C_4") (pintype "bidirectional"))
      (node (ref "IC4") (pin "45") (pinfunction "LPTIM1_OUT/PB8_45") (pintype "bidirectional"))
    )
    (net (code "14") (name "GND") (class "Default")
      (node (ref "C1") (pin "1") (pinfunction "1_1") (pintype "bidirectional"))
      (node (ref "C10") (pin "1") (pinfunction "1_1") (pintype "bidirectional"))
      (node (ref "C101") (pin "1") (pinfunction "1_1") (pintype "bidirectional"))
      (node (ref "C102") (pin "1") (pinfunction "1_1") (pintype "bidirectional"))
      (node (ref "C103") (pin "1") (pinfunction "1_1") (pintype "bidirectional"))
      (node (ref "C104") (pin "1") (pinfunction "1_1") (pintype "bidirectional"))
      (node (ref "C105") (pin "2") (pinfunction "2_2") (pintype "bidirectional"))
      (node (ref "C106") (pin "1") (pinfunction "1_1") (pintype "bidirectional"))
      (node (ref "C107") (pin "1") (pinfunction "1_1") (pintype "bidirectional"))
      (node (ref "C108") (pin "1") (pinfunction "1_1") (pintype "bidirectional"))
      (node (ref "C109") (pin "1") (pinfunction "1_1") (pintype "bidirectional"))
      (node (ref "C11") (pin "1") (pinfunction "1_1") (pintype "bidirectional"))
      (node (ref "C12") (pin "1") (pinfunction "1_1") (pintype "bidirectional"))
      (node (ref "C13") (pin "1") (pinfunction "1_1") (pintype "bidirectional"))
      (node (ref "C15") (pin "1") (pinfunction "1_1") (pintype "bidirectional"))
      (node (ref "C16") (pin "1") (pinfunction "1_1") (pintype "bidirectional"))
      (node (ref "C17") (pin "2") (pinfunction "2_2") (pintype "bidirectional"))
      (node (ref "C18") (pin "1") (pinfunction "1_1") (pintype "bidirectional"))
      (node (ref "C19") (pin "1") (pinfunction "1_1") (pintype "bidirectional"))
      (node (ref "C2") (pin "1") (pinfunction "1_1") (pintype "bidirectional"))
      (node (ref "C20") (pin "2") (pinfunction "2_2") (pintype "bidirectional"))
      (node (ref "C201") (pin "1") (pinfunction "1_1") (pintype "bidirectional"))
      (node (ref "C202") (pin "1") (pinfunction "1_1") (pintype "bidirectional"))
      (node (ref "C203") (pin "1") (pinfunction "1_1") (pintype "bidirectional"))
      (node (ref "C204") (pin "1") (pinfunction "1_1") (pintype "bidirectional"))
      (node (ref "C205") (pin "2") (pinfunction "2_2") (pintype "bidirectional"))
      (node (ref "C206") (pin "1") (pinfunction "1_1") (pintype "bidirectional"))
      (node (ref "C207") (pin "1") (pinfunction "1_1") (pintype "bidirectional"))
      (node (ref "C208") (pin "1") (pinfunction "1_1") (pintype "bidirectional"))
      (node (ref "C209") (pin "1") (pinfunction "1_1") (pintype "bidirectional"))
      (node (ref "C301") (pin "1") (pinfunction "1_1") (pintype "bidirectional"))
      (node (ref "C302") (pin "1") (pinfunction "1_1") (pintype "bidirectional"))
      (node (ref "C303") (pin "1") (pinfunction "1_1") (pintype "bidirectional"))
      (node (ref "C304") (pin "1") (pinfunction "1_1") (pintype "bidirectional"))
      (node (ref "C305") (pin "2") (pinfunction "2_2") (pintype "bidirectional"))
      (node (ref "C306") (pin "1") (pinfunction "1_1") (pintype "bidirectional"))
      (node (ref "C307") (pin "1") (pinfunction "1_1") (pintype "bidirectional"))
      (node (ref "C308") (pin "1") (pinfunction "1_1") (pintype "bidirectional"))
      (node (ref "C309") (pin "1") (pinfunction "1_1") (pintype "bidirectional"))
      (node (ref "C4") (pin "2") (pinfunction "2_2") (pintype "bidirectional"))
      (node (ref "C401") (pin "1") (pinfunction "1_1") (pintype "bidirectional"))
      (node (ref "C402") (pin "1") (pinfunction "1_1") (pintype "bidirectional"))
      (node (ref "C403") (pin "1") (pinfunction "1_1") (pintype "bidirectional"))
      (node (ref "C404") (pin "1") (pinfunction "1_1") (pintype "bidirectional"))
      (node (ref "C405") (pin "2") (pinfunction "2_2") (pintype "bidirectional"))
      (node (ref "C406") (pin "1") (pinfunction "1_1") (pintype "bidirectional"))
      (node (ref "C407") (pin "1") (pinfunction "1_1") (pintype "bidirectional"))
      (node (ref "C408") (pin "1") (pinfunction "1_1") (pintype "bidirectional"))
      (node (ref "C409") (pin "1") (pinfunction "1_1") (pintype "bidirectional"))
      (node (ref "C5") (pin "2") (pinfunction "2_2") (pintype "bidirectional"))
      (node (ref "C6") (pin "2") (pinfunction "2_2") (pintype "bidirectional"))
      (node (ref "C8") (pin "1") (pinfunction "1_1") (pintype "bidirectional"))
      (node (ref "C9") (pin "1") (pinfunction "1_1") (pintype "bidirectional"))
      (node (ref "D1") (pin "2") (pinfunction "A_2") (pintype "bidirectional"))
      (node (ref "DS1") (pin "1") (pinfunction "VSS_1") (pintype "bidirectional"))
      (node (ref "DS1") (pin "10") (pinfunction "DB3_10") (pintype "bidirectional"))
      (node (ref "DS1") (pin "11") (pinfunction "DB4_11") (pintype "bidirectional"))
      (node (ref "DS1") (pin "12") (pinfunction "DB5_12") (pintype "bidirectional"))
      (node (ref "DS1") (pin "13") (pinfunction "DB6_13") (pintype "bidirectional"))
      (node (ref "DS1") (pin "14") (pinfunction "DB7_14") (pintype "bidirectional"))
      (node (ref "DS1") (pin "19") (pinfunction "BS1_19") (pintype "bidirectional"))
      (node (ref "DS1") (pin "5") (pinfunction "~{WR}/VSS_5") (pintype "bidirectional"))
      (node (ref "DS1") (pin "6") (pinfunction "~{RD}/VSS_6") (pintype "bidirectional"))
      (node (ref "IC1") (pin "4") (pinfunction "GND_4") (pintype "power_in"))
      (node (ref "IC101") (pin "4") (pinfunction "V-_4") (pintype "power_in"))
      (node (ref "IC102") (pin "4") (pinfunction "GND_4") (pintype "power_in"))
      (node (ref "IC103") (pin "4") (pinfunction "GND_4") (pintype "power_in"))
      (node (ref "IC104") (pin "4") (pinfunction "V-_4") (pintype "power_in"))
      (node (ref "IC105") (pin "4") (pinfunction "V-_4") (pintype "power_in"))
      (node (ref "IC2") (pin "4") (pinfunction "GND_4") (pintype "bidirectional"))
      (node (ref "IC2") (pin "6") (pinfunction "GND_6") (pintype "bidirectional"))
      (node (ref "IC201") (pin "4") (pinfunction "V-_4") (pintype "power_in"))
      (node (ref "IC202") (pin "4") (pinfunction "GND_4") (pintype "power_in"))
      (node (ref "IC203") (pin "4") (pinfunction "GND_4") (pintype "power_in"))
      (node (ref "IC204") (pin "4") (pinfunction "V-_4") (pintype "power_in"))
      (node (ref "IC205") (pin "4") (pinfunction "V-_4") (pintype "power_in"))
      (node (ref "IC3") (pin "4") (pinfunction "GND_4") (pintype "power_in"))
      (node (ref "IC301") (pin "4") (pinfunction "V-_4") (pintype "power_in"))
      (node (ref "IC302") (pin "4") (pinfunction "GND_4") (pintype "power_in"))
      (node (ref "IC303") (pin "4") (pinfunction "GND_4") (pintype "power_in"))
      (node (ref "IC304") (pin "4") (pinfunction "V-_4") (pintype "power_in"))
      (node (ref "IC305") (pin "4") (pinfunction "V-_4") (pintype "power_in"))
      (node (ref "IC4") (pin "23") (pinfunction "VSS_1_23") (pintype "bidirectional"))
      (node (ref "IC4") (pin "35") (pinfunction "VSS_2_35") (pintype "bidirectional"))
      (node (ref "IC4") (pin "46") (pinfunction "VSS_3_46") (pintype "bidirectional"))
      (node (ref "IC4") (pin "47") (pinfunction "PDR_ON_47") (pintype "bidirectional"))
      (node (ref "IC4") (pin "8") (pinfunction "VSSA/VREF-_8") (pintype "bidirectional"))
      (node (ref "IC401") (pin "4") (pinfunction "V-_4") (pintype "power_in"))
      (node (ref "IC402") (pin "4") (pinfunction "GND_4") (pintype "power_in"))
      (node (ref "IC403") (pin "4") (pinfunction "GND_4") (pintype "power_in"))
      (node (ref "IC404") (pin "4") (pinfunction "V-_4") (pintype "power_in"))
      (node (ref "IC405") (pin "4") (pinfunction "V-_4") (pintype "power_in"))
      (node (ref "IC5") (pin "4") (pinfunction "GND_4") (pintype "power_in"))
      (node (ref "J1") (pin "2") (pinfunction "2_2") (pintype "passive"))
      (node (ref "J101") (pin "2") (pinfunction "2_2") (pintype "passive"))
      (node (ref "J102") (pin "2") (pinfunction "2_2") (pintype "passive"))
      (node (ref "J2") (pin "5") (pinfunction "5_5") (pintype "passive"))
      (node (ref "J2") (pin "6") (pinfunction "6_6") (pintype "passive"))
      (node (ref "J201") (pin "2") (pinfunction "2_2") (pintype "passive"))
      (node (ref "J202") (pin "2") (pinfunction "2_2") (pintype "passive"))
      (node (ref "J3") (pin "2") (pinfunction "2_2") (pintype "passive"))
      (node (ref "J301") (pin "2") (pinfunction "2_2") (pintype "passive"))
      (node (ref "J302") (pin "2") (pinfunction "2_2") (pintype "passive"))
      (node (ref "J4") (pin "1") (pinfunction "1_1") (pintype "passive"))
      (node (ref "J4") (pin "2") (pinfunction "2_2") (pintype "passive"))
      (node (ref "J401") (pin "2") (pinfunction "2_2") (pintype "passive"))
      (node (ref "J402") (pin "2") (pinfunction "2_2") (pintype "passive"))
      (node (ref "J5") (pin "1") (pinfunction "1_1") (pintype "passive"))
      (node (ref "J5") (pin "2") (pinfunction "2_2") (pintype "passive"))
      (node (ref "J6") (pin "1") (pinfunction "1_1") (pintype "passive"))
      (node (ref "J7") (pin "6") (pinfunction "6_6") (pintype "passive"))
      (node (ref "J9") (pin "1") (pinfunction "1_1") (pintype "passive"))
      (node (ref "M1") (pin "1") (pinfunction "V-1_1") (pintype "power_in"))
      (node (ref "M1") (pin "2") (pinfunction "V-2_2") (pintype "power_in"))
      (node (ref "M1") (pin "3") (pinfunction "V-3_3") (pintype "power_in"))
      (node (ref "M1") (pin "4") (pinfunction "V-4_4") (pintype "power_in"))
      (node (ref "Q101") (pin "5") (pinfunction "S_5") (pintype "bidirectional"))
      (node (ref "Q102") (pin "5") (pinfunction "S_5") (pintype "bidirectional"))
      (node (ref "Q201") (pin "5") (pinfunction "S_5") (pintype "bidirectional"))
      (node (ref "Q202") (pin "5") (pinfunction "S_5") (pintype "bidirectional"))
      (node (ref "Q301") (pin "5") (pinfunction "S_5") (pintype "bidirectional"))
      (node (ref "Q302") (pin "5") (pinfunction "S_5") (pintype "bidirectional"))
      (node (ref "Q401") (pin "5") (pinfunction "S_5") (pintype "bidirectional"))
      (node (ref "Q402") (pin "5") (pinfunction "S_5") (pintype "bidirectional"))
      (node (ref "R10") (pin "1") (pinfunction "1_1") (pintype "passive"))
      (node (ref "R101") (pin "1") (pinfunction "1_1") (pintype "passive"))
      (node (ref "R102") (pin "1") (pinfunction "1_1") (pintype "passive"))
      (node (ref "R109") (pin "1") (pinfunction "START_1") (pintype "passive"))
      (node (ref "R11") (pin "1") (pinfunction "1_1") (pintype "passive"))
      (node (ref "R110") (pin "1") (pinfunction "START_1") (pintype "passive"))
      (node (ref "R116") (pin "1") (pinfunction "1_1") (pintype "passive"))
      (node (ref "R117") (pin "1") (pinfunction "1_1") (pintype "passive"))
      (node (ref "R12") (pin "2") (pinfunction "2_2") (pintype "passive"))
      (node (ref "R14") (pin "1") (pinfunction "1_1") (pintype "passive"))
      (node (ref "R2") (pin "2") (pinfunction "2_2") (pintype "passive"))
      (node (ref "R201") (pin "1") (pinfunction "1_1") (pintype "passive"))
      (node (ref "R202") (pin "1") (pinfunction "1_1") (pintype "passive"))
      (node (ref "R209") (pin "1") (pinfunction "START_1") (pintype "passive"))
      (node (ref "R210") (pin "1") (pinfunction "START_1") (pintype "passive"))
      (node (ref "R216") (pin "1") (pinfunction "1_1") (pintype "passive"))
      (node (ref "R217") (pin "1") (pinfunction "1_1") (pintype "passive"))
      (node (ref "R301") (pin "1") (pinfunction "1_1") (pintype "passive"))
      (node (ref "R302") (pin "1") (pinfunction "1_1") (pintype "passive"))
      (node (ref "R309") (pin "1") (pinfunction "START_1") (pintype "passive"))
      (node (ref "R310") (pin "1") (pinfunction "START_1") (pintype "passive"))
      (node (ref "R316") (pin "1") (pinfunction "1_1") (pintype "passive"))
      (node (ref "R317") (pin "1") (pinfunction "1_1") (pintype "passive"))
      (node (ref "R401") (pin "1") (pinfunction "1_1") (pintype "passive"))
      (node (ref "R402") (pin "1") (pinfunction "1_1") (pintype "passive"))
      (node (ref "R409") (pin "1") (pinfunction "START_1") (pintype "passive"))
      (node (ref "R410") (pin "1") (pinfunction "START_1") (pintype "passive"))
      (node (ref "R416") (pin "1") (pinfunction "1_1") (pintype "passive"))
      (node (ref "R417") (pin "1") (pinfunction "1_1") (pintype "passive"))
      (node (ref "S1") (pin "1") (pinfunction "P$1_1") (pintype "passive"))
      (node (ref "S1") (pin "MH1") (pinfunction "G1_MH1") (pintype "passive"))
      (node (ref "S1") (pin "MH2") (pinfunction "G1_MH2") (pintype "passive"))
      (node (ref "S2") (pin "1") (pinfunction "P$1_1") (pintype "passive"))
      (node (ref "S2") (pin "MH1") (pinfunction "G1_MH1") (pintype "passive"))
      (node (ref "S2") (pin "MH2") (pinfunction "G1_MH2") (pintype "passive"))
      (node (ref "S3") (pin "10") (pinfunction "P$2_10") (pintype "passive"))
      (node (ref "S3") (pin "12") (pinfunction "P$2_12") (pintype "passive"))
      (node (ref "S3") (pin "14") (pinfunction "P$2_14") (pintype "passive"))
      (node (ref "S3") (pin "16") (pinfunction "P$2_16") (pintype "passive"))
      (node (ref "S3") (pin "2") (pinfunction "P$2_2") (pintype "passive"))
      (node (ref "S3") (pin "4") (pinfunction "P$2_4") (pintype "passive"))
      (node (ref "S3") (pin "6") (pinfunction "P$2_6") (pintype "passive"))
      (node (ref "Y1") (pin "2") (pinfunction "G1_2") (pintype "passive"))
      (node (ref "Y1") (pin "4") (pinfunction "G1_4") (pintype "passive"))
    )
    (net (code "15") (name "GPIO0") (class "Default")
      (node (ref "IC4") (pin "29") (pinfunction "USART1_CK/PA8_29") (pintype "bidirectional"))
      (node (ref "J2") (pin "1") (pinfunction "1_1") (pintype "passive"))
    )
    (net (code "16") (name "GPIO1") (class "Default")
      (node (ref "IC4") (pin "41") (pinfunction "I2C1_SMBA/PB5_41") (pintype "bidirectional"))
      (node (ref "J2") (pin "4") (pinfunction "4_4") (pintype "passive"))
      (node (ref "J6") (pin "3") (pinfunction "3_3") (pintype "passive"))
      (node (ref "S2") (pin "3") (pinfunction "P$2_3") (pintype "passive"))
    )
    (net (code "17") (name "Net-(D1-K)") (class "Default")
      (node (ref "C14") (pin "1") (pinfunction "1_1") (pintype "bidirectional"))
      (node (ref "D1") (pin "1") (pinfunction "K_1") (pintype "bidirectional"))
      (node (ref "IC4") (pin "7") (pinfunction "NRST_7") (pintype "bidirectional"))
      (node (ref "R4") (pin "1") (pinfunction "1_1") (pintype "passive"))
    )
    (net (code "18") (name "Net-(D2-K)") (class "Default")
      (node (ref "C20") (pin "1") (pinfunction "1_1") (pintype "bidirectional"))
      (node (ref "D2") (pin "1") (pinfunction "K_1") (pintype "bidirectional"))
      (node (ref "DS1") (pin "2") (pinfunction "VDD_2") (pintype "bidirectional"))
      (node (ref "R13") (pin "2") (pinfunction "2_2") (pintype "passive"))
    )
    (net (code "19") (name "Net-(DS1-BS0)") (class "Default")
      (node (ref "DS1") (pin "20") (pinfunction "BS0_20") (pintype "bidirectional"))
      (node (ref "R13") (pin "1") (pinfunction "1_1") (pintype "passive"))
      (node (ref "R14") (pin "2") (pinfunction "2_2") (pintype "passive"))
    )
    (net (code "20") (name "Net-(IC1-BST)") (class "Default")
      (node (ref "C3") (pin "1") (pinfunction "1_1") (pintype "bidirectional"))
      (node (ref "IC1") (pin "6") (pinfunction "BST_6") (pintype "input"))
    )
    (net (code "21") (name "Net-(IC1-EN)") (class "Default")
      (node (ref "C4") (pin "1") (pinfunction "1_1") (pintype "bidirectional"))
      (node (ref "IC1") (pin "2") (pinfunction "EN_2") (pintype "input"))
      (node (ref "IC1") (pin "3") (pinfunction "VIN_3") (pintype "power_in"))
      (node (ref "M1") (pin "8") (pinfunction "V+4_8") (pintype "power_in"))
    )
    (net (code "22") (name "Net-(IC1-FB)") (class "Default")
      (node (ref "C7") (pin "1") (pinfunction "1_1") (pintype "bidirectional"))
      (node (ref "IC1") (pin "1") (pinfunction "FB_1") (pintype "input"))
      (node (ref "R1") (pin "1") (pinfunction "1_1") (pintype "passive"))
      (node (ref "R2") (pin "1") (pinfunction "1_1") (pintype "passive"))
    )
    (net (code "23") (name "Net-(IC1-SW)") (class "Default")
      (node (ref "C3") (pin "2") (pinfunction "2_2") (pintype "bidirectional"))
      (node (ref "IC1") (pin "5") (pinfunction "SW_5") (pintype "output"))
      (node (ref "L1") (pin "1") (pinfunction "1_1") (pintype "bidirectional"))
    )
    (net (code "24") (name "Net-(IC3A-I0)") (class "Default")
      (node (ref "C17") (pin "1") (pinfunction "1_1") (pintype "bidirectional"))
      (node (ref "IC3") (pin "1") (pinfunction "I0_1") (pintype "input"))
      (node (ref "IC3") (pin "2") (pinfunction "I1_2") (pintype "input"))
      (node (ref "IC3") (pin "5") (pinfunction "I0_5") (pintype "input"))
      (node (ref "IC3") (pin "6") (pinfunction "I1_6") (pintype "input"))
      (node (ref "R7") (pin "2") (pinfunction "2_2") (pintype "passive"))
    )
    (net (code "25") (name "Net-(IC3A-O)") (class "Default")
      (node (ref "C14") (pin "2") (pinfunction "2_2") (pintype "bidirectional"))
      (node (ref "IC3") (pin "7") (pinfunction "O_7") (pintype "output"))
    )
    (net (code "26") (name "Net-(IC4A-BOOT0)") (class "Default")
      (node (ref "IC4") (pin "44") (pinfunction "BOOT0_44") (pintype "bidirectional"))
      (node (ref "R10") (pin "2") (pinfunction "2_2") (pintype "passive"))
      (node (ref "S3") (pin "7") (pinfunction "P$1_7") (pintype "passive"))
    )
    (net (code "27") (name "Net-(IC4A-JTDI{slash}PA15)") (class "Default")
      (node (ref "IC4") (pin "38") (pinfunction "JTDI/PA15_38") (pintype "bidirectional"))
      (node (ref "IC5") (pin "7") (pinfunction "O_7") (pintype "output"))
    )
    (net (code "28") (name "Net-(IC4A-PH0{slash}OSC_IN)") (class "Default")
      (node (ref "C15") (pin "2") (pinfunction "2_2") (pintype "bidirectional"))
      (node (ref "IC4") (pin "5") (pinfunction "PH0/OSC_IN_5") (pintype "bidirectional"))
      (node (ref "Y1") (pin "3") (pinfunction "OI_3") (pintype "passive"))
    )
    (net (code "29") (name "Net-(IC4A-PH1{slash}OSC_OUT)") (class "Default")
      (node (ref "IC4") (pin "6") (pinfunction "PH1/OSC_OUT_6") (pintype "bidirectional"))
      (node (ref "R8") (pin "2") (pinfunction "2_2") (pintype "passive"))
    )
    (net (code "30") (name "Net-(IC4A-USART1_RX{slash}PA10)") (class "Default")
      (node (ref "IC4") (pin "31") (pinfunction "USART1_RX/PA10_31") (pintype "bidirectional"))
      (node (ref "R5") (pin "1") (pinfunction "1_1") (pintype "passive"))
    )
    (net (code "31") (name "Net-(IC4A-USART1_TX{slash}PA9)") (class "Default")
      (node (ref "IC4") (pin "30") (pinfunction "USART1_TX/PA9_30") (pintype "bidirectional"))
      (node (ref "R3") (pin "1") (pinfunction "1_1") (pintype "passive"))
    )
    (net (code "32") (name "Net-(IC4A-VCAP_1)") (class "Default")
      (node (ref "C19") (pin "2") (pinfunction "2_2") (pintype "bidirectional"))
      (node (ref "IC4") (pin "22") (pinfunction "VCAP_1_22") (pintype "bidirectional"))
    )
    (net (code "33") (name "Net-(IC4A-VDDA{slash}VREF+)") (class "Default")
      (node (ref "C18") (pin "2") (pinfunction "2_2") (pintype "bidirectional"))
      (node (ref "IC4") (pin "9") (pinfunction "VDDA/VREF+_9") (pintype "bidirectional"))
      (node (ref "R9") (pin "1") (pinfunction "1_1") (pintype "passive"))
    )
    (net (code "34") (name "Net-(IC4B-A8{slash}PB0)") (class "Default")
      (node (ref "IC4") (pin "18") (pinfunction "A8/PB0_18") (pintype "bidirectional"))
      (node (ref "S3") (pin "15") (pinfunction "P$1_15") (pintype "passive"))
    )
    (net (code "35") (name "Net-(IC4B-A9{slash}PB1)") (class "Default")
      (node (ref "IC4") (pin "19") (pinfunction "A9/PB1_19") (pintype "bidirectional"))
      (node (ref "S3") (pin "13") (pinfunction "P$1_13") (pintype "passive"))
    )
    (net (code "36") (name "Net-(IC4B-BOOT1{slash}PB2)") (class "Default")
      (node (ref "IC4") (pin "20") (pinfunction "BOOT1/PB2_20") (pintype "bidirectional"))
      (node (ref "S3") (pin "11") (pinfunction "P$1_11") (pintype "passive"))
    )
    (net (code "37") (name "Net-(IC4B-I2C1_SCL{slash}PB6)") (class "Default")
      (node (ref "IC4") (pin "42") (pinfunction "I2C1_SCL/PB6_42") (pintype "bidirectional"))
      (node (ref "J6") (pin "4") (pinfunction "4_4") (pintype "passive"))
    )
    (net (code "38") (name "Net-(IC4B-I2C1_SDA{slash}PB7)") (class "Default")
      (node (ref "IC4") (pin "43") (pinfunction "I2C1_SDA/PB7_43") (pintype "bidirectional"))
      (node (ref "J6") (pin "5") (pinfunction "5_5") (pintype "passive"))
    )
    (net (code "39") (name "Net-(IC4B-I2C4_SDA{slash}SPI2_MISO{slash}PB14)") (class "Default")
      (node (ref "IC4") (pin "27") (pinfunction "I2C4_SDA/SPI2_MISO/PB14_27") (pintype "bidirectional"))
      (node (ref "J6") (pin "2") (pinfunction "2_2") (pintype "passive"))
    )
    (net (code "40") (name "Net-(IC4B-JTDO{slash}PB3)") (class "Default")
      (node (ref "IC4") (pin "39") (pinfunction "JTDO/PB3_39") (pintype "bidirectional"))
      (node (ref "S3") (pin "9") (pinfunction "P$1_9") (pintype "passive"))
    )
    (net (code "41") (name "Net-(IC4B-JTRST{slash}PB4)") (class "Default")
      (node (ref "IC4") (pin "40") (pinfunction "JTRST/PB4_40") (pintype "bidirectional"))
      (node (ref "IC5") (pin "5") (pinfunction "I0_5") (pintype "input"))
      (node (ref "IC5") (pin "6") (pinfunction "I1_6") (pintype "input"))
      (node (ref "R12") (pin "1") (pinfunction "1_1") (pintype "passive"))
    )
    (net (code "42") (name "Net-(IC4B-PC13)") (class "Default")
      (node (ref "IC4") (pin "2") (pinfunction "PC13_2") (pintype "bidirectional"))
      (node (ref "S3") (pin "5") (pinfunction "P$1_5") (pintype "passive"))
    )
    (net (code "43") (name "Net-(IC4B-PC14{slash}OSC32_IN)") (class "Default")
      (node (ref "IC4") (pin "3") (pinfunction "PC14/OSC32_IN_3") (pintype "bidirectional"))
      (node (ref "S3") (pin "3") (pinfunction "P$1_3") (pintype "passive"))
    )
    (net (code "44") (name "Net-(IC4B-PC15{slash}OSC32_OUT)") (class "Default")
      (node (ref "IC4") (pin "4") (pinfunction "PC15/OSC32_OUT_4") (pintype "bidirectional"))
      (node (ref "S3") (pin "1") (pinfunction "P$1_1") (pintype "passive"))
    )
    (net (code "45") (name "Net-(IC5A-I0)") (class "Default")
      (node (ref "IC5") (pin "1") (pinfunction "I0_1") (pintype "input"))
      (node (ref "IC5") (pin "2") (pinfunction "I1_2") (pintype "input"))
      (node (ref "J3") (pin "1") (pinfunction "1_1") (pintype "passive"))
      (node (ref "R11") (pin "2") (pinfunction "2_2") (pintype "passive"))
    )
    (net (code "46") (name "Net-(IC101A-+IN)") (class "Default")
      (node (ref "IC101") (pin "3") (pinfunction "+IN_3") (pintype "input"))
      (node (ref "J101") (pin "1") (pinfunction "1_1") (pintype "passive"))
      (node (ref "R101") (pin "2") (pinfunction "2_2") (pintype "passive"))
    )
    (net (code "47") (name "Net-(IC101A--IN)") (class "Default")
      (node (ref "IC101") (pin "1") (pinfunction "OUT_1") (pintype "output"))
      (node (ref "IC101") (pin "2") (pinfunction "-IN_2") (pintype "input"))
      (node (ref "R103") (pin "2") (pinfunction "2_2") (pintype "passive"))
    )
    (net (code "48") (name "Net-(IC101B-+IN)") (class "Default")
      (node (ref "IC101") (pin "5") (pinfunction "+IN_5") (pintype "input"))
      (node (ref "J102") (pin "1") (pinfunction "1_1") (pintype "passive"))
      (node (ref "R102") (pin "2") (pinfunction "2_2") (pintype "passive"))
    )
    (net (code "49") (name "Net-(IC101B--IN)") (class "Default")
      (node (ref "IC101") (pin "6") (pinfunction "-IN_6") (pintype "input"))
      (node (ref "IC101") (pin "7") (pinfunction "OUT_7") (pintype "output"))
      (node (ref "R104") (pin "2") (pinfunction "2_2") (pintype "passive"))
    )
    (net (code "50") (name "Net-(IC102A-O)") (class "Default")
      (node (ref "IC102") (pin "7") (pinfunction "O_7") (pintype "output"))
      (node (ref "Q101") (pin "3") (pinfunction "G_3") (pintype "passive"))
    )
    (net (code "51") (name "Net-(IC102B-O)") (class "Default")
      (node (ref "IC102") (pin "3") (pinfunction "O_3") (pintype "output"))
      (node (ref "Q101") (pin "1") (pinfunction "G_1") (pintype "bidirectional"))
    )
    (net (code "52") (name "Net-(IC103A-O)") (class "Default")
      (node (ref "IC103") (pin "7") (pinfunction "O_7") (pintype "output"))
      (node (ref "Q102") (pin "3") (pinfunction "G_3") (pintype "passive"))
    )
    (net (code "53") (name "Net-(IC103B-O)") (class "Default")
      (node (ref "IC103") (pin "3") (pinfunction "O_3") (pintype "output"))
      (node (ref "Q102") (pin "1") (pinfunction "G_1") (pintype "bidirectional"))
    )
    (net (code "54") (name "Net-(IC104A-+IN)") (class "Default")
      (node (ref "IC104") (pin "3") (pinfunction "+IN_3") (pintype "input"))
      (node (ref "IC105") (pin "3") (pinfunction "+IN_3") (pintype "input"))
      (node (ref "R109") (pin "2") (pinfunction "WIPER_2") (pintype "passive"))
    )
    (net (code "55") (name "Net-(IC104B-+IN)") (class "Default")
      (node (ref "IC104") (pin "5") (pinfunction "+IN_5") (pintype "input"))
      (node (ref "IC105") (pin "5") (pinfunction "+IN_5") (pintype "input"))
      (node (ref "R110") (pin "2") (pinfunction "WIPER_2") (pintype "passive"))
    )
    (net (code "56") (name "Net-(IC105A--IN)") (class "Default")
      (node (ref "IC105") (pin "2") (pinfunction "-IN_2") (pintype "input"))
      (node (ref "Q103") (pin "1") (pinfunction "S_1") (pintype "bidirectional"))
      (node (ref "Q103") (pin "10") (pinfunction "S_10") (pintype "bidirectional"))
      (node (ref "Q103") (pin "2") (pinfunction "S_2") (pintype "bidirectional"))
      (node (ref "Q103") (pin "3") (pinfunction "S_3") (pintype "bidirectional"))
      (node (ref "R111") (pin "1") (pinfunction "1_1") (pintype "passive"))
      (node (ref "R116") (pin "2") (pinfunction "2_2") (pintype "passive"))
    )
    (net (code "57") (name "Net-(IC105A-OUT)") (class "Default")
      (node (ref "IC105") (pin "1") (pinfunction "OUT_1") (pintype "output"))
      (node (ref "R114") (pin "1") (pinfunction "1_1") (pintype "passive"))
    )
    (net (code "58") (name "Net-(IC105A-V+)") (class "Default")
      (node (ref "IC105") (pin "8") (pinfunction "V+_8") (pintype "power_in"))
      (node (ref "R113") (pin "1") (pinfunction "1_1") (pintype "passive"))
    )
    (net (code "59") (name "Net-(IC105B--IN)") (class "Default")
      (node (ref "IC105") (pin "6") (pinfunction "-IN_6") (pintype "input"))
      (node (ref "Q104") (pin "1") (pinfunction "S_1") (pintype "bidirectional"))
      (node (ref "Q104") (pin "10") (pinfunction "S_10") (pintype "bidirectional"))
      (node (ref "Q104") (pin "2") (pinfunction "S_2") (pintype "bidirectional"))
      (node (ref "Q104") (pin "3") (pinfunction "S_3") (pintype "bidirectional"))
      (node (ref "R112") (pin "1") (pinfunction "1_1") (pintype "passive"))
      (node (ref "R117") (pin "2") (pinfunction "2_2") (pintype "passive"))
    )
    (net (code "60") (name "Net-(IC105B-OUT)") (class "Default")
      (node (ref "IC105") (pin "7") (pinfunction "OUT_7") (pintype "output"))
      (node (ref "R115") (pin "1") (pinfunction "1_1") (pintype "passive"))
    )
    (net (code "61") (name "Net-(IC201A-+IN)") (class "Default")
      (node (ref "IC201") (pin "3") (pinfunction "+IN_3") (pintype "input"))
      (node (ref "J201") (pin "1") (pinfunction "1_1") (pintype "passive"))
      (node (ref "R201") (pin "2") (pinfunction "2_2") (pintype "passive"))
    )
    (net (code "62") (name "Net-(IC201A--IN)") (class "Default")
      (node (ref "IC201") (pin "1") (pinfunction "OUT_1") (pintype "output"))
      (node (ref "IC201") (pin "2") (pinfunction "-IN_2") (pintype "input"))
      (node (ref "R203") (pin "2") (pinfunction "2_2") (pintype "passive"))
    )
    (net (code "63") (name "Net-(IC201B-+IN)") (class "Default")
      (node (ref "IC201") (pin "5") (pinfunction "+IN_5") (pintype "input"))
      (node (ref "J202") (pin "1") (pinfunction "1_1") (pintype "passive"))
      (node (ref "R202") (pin "2") (pinfunction "2_2") (pintype "passive"))
    )
    (net (code "64") (name "Net-(IC201B--IN)") (class "Default")
      (node (ref "IC201") (pin "6") (pinfunction "-IN_6") (pintype "input"))
      (node (ref "IC201") (pin "7") (pinfunction "OUT_7") (pintype "output"))
      (node (ref "R204") (pin "2") (pinfunction "2_2") (pintype "passive"))
    )
    (net (code "65") (name "Net-(IC202A-O)") (class "Default")
      (node (ref "IC202") (pin "7") (pinfunction "O_7") (pintype "output"))
      (node (ref "Q201") (pin "3") (pinfunction "G_3") (pintype "passive"))
    )
    (net (code "66") (name "Net-(IC202B-O)") (class "Default")
      (node (ref "IC202") (pin "3") (pinfunction "O_3") (pintype "output"))
      (node (ref "Q201") (pin "1") (pinfunction "G_1") (pintype "bidirectional"))
    )
    (net (code "67") (name "Net-(IC203A-O)") (class "Default")
      (node (ref "IC203") (pin "7") (pinfunction "O_7") (pintype "output"))
      (node (ref "Q202") (pin "3") (pinfunction "G_3") (pintype "passive"))
    )
    (net (code "68") (name "Net-(IC203B-O)") (class "Default")
      (node (ref "IC203") (pin "3") (pinfunction "O_3") (pintype "output"))
      (node (ref "Q202") (pin "1") (pinfunction "G_1") (pintype "bidirectional"))
    )
    (net (code "69") (name "Net-(IC204A-+IN)") (class "Default")
      (node (ref "IC204") (pin "3") (pinfunction "+IN_3") (pintype "input"))
      (node (ref "IC205") (pin "3") (pinfunction "+IN_3") (pintype "input"))
      (node (ref "R209") (pin "2") (pinfunction "WIPER_2") (pintype "passive"))
    )
    (net (code "70") (name "Net-(IC204B-+IN)") (class "Default")
      (node (ref "IC204") (pin "5") (pinfunction "+IN_5") (pintype "input"))
      (node (ref "IC205") (pin "5") (pinfunction "+IN_5") (pintype "input"))
      (node (ref "R210") (pin "2") (pinfunction "WIPER_2") (pintype "passive"))
    )
    (net (code "71") (name "Net-(IC205A--IN)") (class "Default")
      (node (ref "IC205") (pin "2") (pinfunction "-IN_2") (pintype "input"))
      (node (ref "Q203") (pin "1") (pinfunction "S_1") (pintype "bidirectional"))
      (node (ref "Q203") (pin "10") (pinfunction "S_10") (pintype "bidirectional"))
      (node (ref "Q203") (pin "2") (pinfunction "S_2") (pintype "bidirectional"))
      (node (ref "Q203") (pin "3") (pinfunction "S_3") (pintype "bidirectional"))
      (node (ref "R211") (pin "1") (pinfunction "1_1") (pintype "passive"))
      (node (ref "R216") (pin "2") (pinfunction "2_2") (pintype "passive"))
    )
    (net (code "72") (name "Net-(IC205A-OUT)") (class "Default")
      (node (ref "IC205") (pin "1") (pinfunction "OUT_1") (pintype "output"))
      (node (ref "R214") (pin "1") (pinfunction "1_1") (pintype "passive"))
    )
    (net (code "73") (name "Net-(IC205A-V+)") (class "Default")
      (node (ref "IC205") (pin "8") (pinfunction "V+_8") (pintype "power_in"))
      (node (ref "R213") (pin "1") (pinfunction "1_1") (pintype "passive"))
    )
    (net (code "74") (name "Net-(IC205B--IN)") (class "Default")
      (node (ref "IC205") (pin "6") (pinfunction "-IN_6") (pintype "input"))
      (node (ref "Q204") (pin "1") (pinfunction "S_1") (pintype "bidirectional"))
      (node (ref "Q204") (pin "10") (pinfunction "S_10") (pintype "bidirectional"))
      (node (ref "Q204") (pin "2") (pinfunction "S_2") (pintype "bidirectional"))
      (node (ref "Q204") (pin "3") (pinfunction "S_3") (pintype "bidirectional"))
      (node (ref "R212") (pin "1") (pinfunction "1_1") (pintype "passive"))
      (node (ref "R217") (pin "2") (pinfunction "2_2") (pintype "passive"))
    )
    (net (code "75") (name "Net-(IC205B-OUT)") (class "Default")
      (node (ref "IC205") (pin "7") (pinfunction "OUT_7") (pintype "output"))
      (node (ref "R215") (pin "1") (pinfunction "1_1") (pintype "passive"))
    )
    (net (code "76") (name "Net-(IC301A-+IN)") (class "Default")
      (node (ref "IC301") (pin "3") (pinfunction "+IN_3") (pintype "input"))
      (node (ref "J301") (pin "1") (pinfunction "1_1") (pintype "passive"))
      (node (ref "R301") (pin "2") (pinfunction "2_2") (pintype "passive"))
    )
    (net (code "77") (name "Net-(IC301A--IN)") (class "Default")
      (node (ref "IC301") (pin "1") (pinfunction "OUT_1") (pintype "output"))
      (node (ref "IC301") (pin "2") (pinfunction "-IN_2") (pintype "input"))
      (node (ref "R303") (pin "2") (pinfunction "2_2") (pintype "passive"))
    )
    (net (code "78") (name "Net-(IC301B-+IN)") (class "Default")
      (node (ref "IC301") (pin "5") (pinfunction "+IN_5") (pintype "input"))
      (node (ref "J302") (pin "1") (pinfunction "1_1") (pintype "passive"))
      (node (ref "R302") (pin "2") (pinfunction "2_2") (pintype "passive"))
    )
    (net (code "79") (name "Net-(IC301B--IN)") (class "Default")
      (node (ref "IC301") (pin "6") (pinfunction "-IN_6") (pintype "input"))
      (node (ref "IC301") (pin "7") (pinfunction "OUT_7") (pintype "output"))
      (node (ref "R304") (pin "2") (pinfunction "2_2") (pintype "passive"))
    )
    (net (code "80") (name "Net-(IC302A-O)") (class "Default")
      (node (ref "IC302") (pin "7") (pinfunction "O_7") (pintype "output"))
      (node (ref "Q301") (pin "3") (pinfunction "G_3") (pintype "passive"))
    )
    (net (code "81") (name "Net-(IC302B-O)") (class "Default")
      (node (ref "IC302") (pin "3") (pinfunction "O_3") (pintype "output"))
      (node (ref "Q301") (pin "1") (pinfunction "G_1") (pintype "bidirectional"))
    )
    (net (code "82") (name "Net-(IC303A-O)") (class "Default")
      (node (ref "IC303") (pin "7") (pinfunction "O_7") (pintype "output"))
      (node (ref "Q302") (pin "3") (pinfunction "G_3") (pintype "passive"))
    )
    (net (code "83") (name "Net-(IC303B-O)") (class "Default")
      (node (ref "IC303") (pin "3") (pinfunction "O_3") (pintype "output"))
      (node (ref "Q302") (pin "1") (pinfunction "G_1") (pintype "bidirectional"))
    )
    (net (code "84") (name "Net-(IC304A-+IN)") (class "Default")
      (node (ref "IC304") (pin "3") (pinfunction "+IN_3") (pintype "input"))
      (node (ref "IC305") (pin "3") (pinfunction "+IN_3") (pintype "input"))
      (node (ref "R309") (pin "2") (pinfunction "WIPER_2") (pintype "passive"))
    )
    (net (code "85") (name "Net-(IC304B-+IN)") (class "Default")
      (node (ref "IC304") (pin "5") (pinfunction "+IN_5") (pintype "input"))
      (node (ref "IC305") (pin "5") (pinfunction "+IN_5") (pintype "input"))
      (node (ref "R310") (pin "2") (pinfunction "WIPER_2") (pintype "passive"))
    )
    (net (code "86") (name "Net-(IC305A--IN)") (class "Default")
      (node (ref "IC305") (pin "2") (pinfunction "-IN_2") (pintype "input"))
      (node (ref "Q303") (pin "1") (pinfunction "S_1") (pintype "bidirectional"))
      (node (ref "Q303") (pin "10") (pinfunction "S_10") (pintype "bidirectional"))
      (node (ref "Q303") (pin "2") (pinfunction "S_2") (pintype "bidirectional"))
      (node (ref "Q303") (pin "3") (pinfunction "S_3") (pintype "bidirectional"))
      (node (ref "R311") (pin "1") (pinfunction "1_1") (pintype "passive"))
      (node (ref "R316") (pin "2") (pinfunction "2_2") (pintype "passive"))
    )
    (net (code "87") (name "Net-(IC305A-OUT)") (class "Default")
      (node (ref "IC305") (pin "1") (pinfunction "OUT_1") (pintype "output"))
      (node (ref "R314") (pin "1") (pinfunction "1_1") (pintype "passive"))
    )
    (net (code "88") (name "Net-(IC305A-V+)") (class "Default")
      (node (ref "IC305") (pin "8") (pinfunction "V+_8") (pintype "power_in"))
      (node (ref "R313") (pin "1") (pinfunction "1_1") (pintype "passive"))
    )
    (net (code "89") (name "Net-(IC305B--IN)") (class "Default")
      (node (ref "IC305") (pin "6") (pinfunction "-IN_6") (pintype "input"))
      (node (ref "Q304") (pin "1") (pinfunction "S_1") (pintype "bidirectional"))
      (node (ref "Q304") (pin "10") (pinfunction "S_10") (pintype "bidirectional"))
      (node (ref "Q304") (pin "2") (pinfunction "S_2") (pintype "bidirectional"))
      (node (ref "Q304") (pin "3") (pinfunction "S_3") (pintype "bidirectional"))
      (node (ref "R312") (pin "1") (pinfunction "1_1") (pintype "passive"))
      (node (ref "R317") (pin "2") (pinfunction "2_2") (pintype "passive"))
    )
    (net (code "90") (name "Net-(IC305B-OUT)") (class "Default")
      (node (ref "IC305") (pin "7") (pinfunction "OUT_7") (pintype "output"))
      (node (ref "R315") (pin "1") (pinfunction "1_1") (pintype "passive"))
    )
    (net (code "91") (name "Net-(IC401A-+IN)") (class "Default")
      (node (ref "IC401") (pin "3") (pinfunction "+IN_3") (pintype "input"))
      (node (ref "J401") (pin "1") (pinfunction "1_1") (pintype "passive"))
      (node (ref "R401") (pin "2") (pinfunction "2_2") (pintype "passive"))
    )
    (net (code "92") (name "Net-(IC401A--IN)") (class "Default")
      (node (ref "IC401") (pin "1") (pinfunction "OUT_1") (pintype "output"))
      (node (ref "IC401") (pin "2") (pinfunction "-IN_2") (pintype "input"))
      (node (ref "R403") (pin "2") (pinfunction "2_2") (pintype "passive"))
    )
    (net (code "93") (name "Net-(IC401B-+IN)") (class "Default")
      (node (ref "IC401") (pin "5") (pinfunction "+IN_5") (pintype "input"))
      (node (ref "J402") (pin "1") (pinfunction "1_1") (pintype "passive"))
      (node (ref "R402") (pin "2") (pinfunction "2_2") (pintype "passive"))
    )
    (net (code "94") (name "Net-(IC401B--IN)") (class "Default")
      (node (ref "IC401") (pin "6") (pinfunction "-IN_6") (pintype "input"))
      (node (ref "IC401") (pin "7") (pinfunction "OUT_7") (pintype "output"))
      (node (ref "R404") (pin "2") (pinfunction "2_2") (pintype "passive"))
    )
    (net (code "95") (name "Net-(IC402A-O)") (class "Default")
      (node (ref "IC402") (pin "7") (pinfunction "O_7") (pintype "output"))
      (node (ref "Q401") (pin "3") (pinfunction "G_3") (pintype "passive"))
    )
    (net (code "96") (name "Net-(IC402B-O)") (class "Default")
      (node (ref "IC402") (pin "3") (pinfunction "O_3") (pintype "output"))
      (node (ref "Q401") (pin "1") (pinfunction "G_1") (pintype "bidirectional"))
    )
    (net (code "97") (name "Net-(IC403A-O)") (class "Default")
      (node (ref "IC403") (pin "7") (pinfunction "O_7") (pintype "output"))
      (node (ref "Q402") (pin "3") (pinfunction "G_3") (pintype "passive"))
    )
    (net (code "98") (name "Net-(IC403B-O)") (class "Default")
      (node (ref "IC403") (pin "3") (pinfunction "O_3") (pintype "output"))
      (node (ref "Q402") (pin "1") (pinfunction "G_1") (pintype "bidirectional"))
    )
    (net (code "99") (name "Net-(IC404A-+IN)") (class "Default")
      (node (ref "IC404") (pin "3") (pinfunction "+IN_3") (pintype "input"))
      (node (ref "IC405") (pin "3") (pinfunction "+IN_3") (pintype "input"))
      (node (ref "R409") (pin "2") (pinfunction "WIPER_2") (pintype "passive"))
    )
    (net (code "100") (name "Net-(IC404B-+IN)") (class "Default")
      (node (ref "IC404") (pin "5") (pinfunction "+IN_5") (pintype "input"))
      (node (ref "IC405") (pin "5") (pinfunction "+IN_5") (pintype "input"))
      (node (ref "R410") (pin "2") (pinfunction "WIPER_2") (pintype "passive"))
    )
    (net (code "101") (name "Net-(IC405A--IN)") (class "Default")
      (node (ref "IC405") (pin "2") (pinfunction "-IN_2") (pintype "input"))
      (node (ref "Q403") (pin "1") (pinfunction "S_1") (pintype "bidirectional"))
      (node (ref "Q403") (pin "10") (pinfunction "S_10") (pintype "bidirectional"))
      (node (ref "Q403") (pin "2") (pinfunction "S_2") (pintype "bidirectional"))
      (node (ref "Q403") (pin "3") (pinfunction "S_3") (pintype "bidirectional"))
      (node (ref "R411") (pin "1") (pinfunction "1_1") (pintype "passive"))
      (node (ref "R416") (pin "2") (pinfunction "2_2") (pintype "passive"))
    )
    (net (code "102") (name "Net-(IC405A-OUT)") (class "Default")
      (node (ref "IC405") (pin "1") (pinfunction "OUT_1") (pintype "output"))
      (node (ref "R414") (pin "1") (pinfunction "1_1") (pintype "passive"))
    )
    (net (code "103") (name "Net-(IC405A-V+)") (class "Default")
      (node (ref "IC405") (pin "8") (pinfunction "V+_8") (pintype "power_in"))
      (node (ref "R413") (pin "1") (pinfunction "1_1") (pintype "passive"))
    )
    (net (code "104") (name "Net-(IC405B--IN)") (class "Default")
      (node (ref "IC405") (pin "6") (pinfunction "-IN_6") (pintype "input"))
      (node (ref "Q404") (pin "1") (pinfunction "S_1") (pintype "bidirectional"))
      (node (ref "Q404") (pin "10") (pinfunction "S_10") (pintype "bidirectional"))
      (node (ref "Q404") (pin "2") (pinfunction "S_2") (pintype "bidirectional"))
      (node (ref "Q404") (pin "3") (pinfunction "S_3") (pintype "bidirectional"))
      (node (ref "R412") (pin "1") (pinfunction "1_1") (pintype "passive"))
      (node (ref "R417") (pin "2") (pinfunction "2_2") (pintype "passive"))
    )
    (net (code "105") (name "Net-(IC405B-OUT)") (class "Default")
      (node (ref "IC405") (pin "7") (pinfunction "OUT_7") (pintype "output"))
      (node (ref "R415") (pin "1") (pinfunction "1_1") (pintype "passive"))
    )
    (net (code "106") (name "Net-(J1-Pad1)") (class "Default")
      (node (ref "J1") (pin "1") (pinfunction "1_1") (pintype "passive"))
      (node (ref "R3") (pin "2") (pinfunction "2_2") (pintype "passive"))
    )
    (net (code "107") (name "Net-(J1-Pad3)") (class "Default")
      (node (ref "J1") (pin "3") (pinfunction "3_3") (pintype "passive"))
      (node (ref "R5") (pin "2") (pinfunction "2_2") (pintype "passive"))
    )
    (net (code "108") (name "Net-(J103-Pad2)") (class "Default")
      (node (ref "J103") (pin "2") (pinfunction "2_2") (pintype "passive"))
      (node (ref "Q103") (pin "5") (pinfunction "D_5") (pintype "bidirectional"))
      (node (ref "Q103") (pin "6") (pinfunction "D_6") (pintype "bidirectional"))
      (node (ref "Q103") (pin "7") (pinfunction "D_7") (pintype "bidirectional"))
      (node (ref "Q103") (pin "8") (pinfunction "D_8") (pintype "bidirectional"))
      (node (ref "Q103") (pin "9") (pinfunction "D_9") (pintype "bidirectional"))
    )
    (net (code "109") (name "Net-(J104-Pad2)") (class "Default")
      (node (ref "J104") (pin "2") (pinfunction "2_2") (pintype "passive"))
      (node (ref "Q104") (pin "5") (pinfunction "D_5") (pintype "bidirectional"))
      (node (ref "Q104") (pin "6") (pinfunction "D_6") (pintype "bidirectional"))
      (node (ref "Q104") (pin "7") (pinfunction "D_7") (pintype "bidirectional"))
      (node (ref "Q104") (pin "8") (pinfunction "D_8") (pintype "bidirectional"))
      (node (ref "Q104") (pin "9") (pinfunction "D_9") (pintype "bidirectional"))
    )
    (net (code "110") (name "Net-(J203-Pad2)") (class "Default")
      (node (ref "J203") (pin "2") (pinfunction "2_2") (pintype "passive"))
      (node (ref "Q203") (pin "5") (pinfunction "D_5") (pintype "bidirectional"))
      (node (ref "Q203") (pin "6") (pinfunction "D_6") (pintype "bidirectional"))
      (node (ref "Q203") (pin "7") (pinfunction "D_7") (pintype "bidirectional"))
      (node (ref "Q203") (pin "8") (pinfunction "D_8") (pintype "bidirectional"))
      (node (ref "Q203") (pin "9") (pinfunction "D_9") (pintype "bidirectional"))
    )
    (net (code "111") (name "Net-(J204-Pad2)") (class "Default")
      (node (ref "J204") (pin "2") (pinfunction "2_2") (pintype "passive"))
      (node (ref "Q204") (pin "5") (pinfunction "D_5") (pintype "bidirectional"))
      (node (ref "Q204") (pin "6") (pinfunction "D_6") (pintype "bidirectional"))
      (node (ref "Q204") (pin "7") (pinfunction "D_7") (pintype "bidirectional"))
      (node (ref "Q204") (pin "8") (pinfunction "D_8") (pintype "bidirectional"))
      (node (ref "Q204") (pin "9") (pinfunction "D_9") (pintype "bidirectional"))
    )
    (net (code "112") (name "Net-(J303-Pad2)") (class "Default")
      (node (ref "J303") (pin "2") (pinfunction "2_2") (pintype "passive"))
      (node (ref "Q303") (pin "5") (pinfunction "D_5") (pintype "bidirectional"))
      (node (ref "Q303") (pin "6") (pinfunction "D_6") (pintype "bidirectional"))
      (node (ref "Q303") (pin "7") (pinfunction "D_7") (pintype "bidirectional"))
      (node (ref "Q303") (pin "8") (pinfunction "D_8") (pintype "bidirectional"))
      (node (ref "Q303") (pin "9") (pinfunction "D_9") (pintype "bidirectional"))
    )
    (net (code "113") (name "Net-(J304-Pad2)") (class "Default")
      (node (ref "J304") (pin "2") (pinfunction "2_2") (pintype "passive"))
      (node (ref "Q304") (pin "5") (pinfunction "D_5") (pintype "bidirectional"))
      (node (ref "Q304") (pin "6") (pinfunction "D_6") (pintype "bidirectional"))
      (node (ref "Q304") (pin "7") (pinfunction "D_7") (pintype "bidirectional"))
      (node (ref "Q304") (pin "8") (pinfunction "D_8") (pintype "bidirectional"))
      (node (ref "Q304") (pin "9") (pinfunction "D_9") (pintype "bidirectional"))
    )
    (net (code "114") (name "Net-(J403-Pad2)") (class "Default")
      (node (ref "J403") (pin "2") (pinfunction "2_2") (pintype "passive"))
      (node (ref "Q403") (pin "5") (pinfunction "D_5") (pintype "bidirectional"))
      (node (ref "Q403") (pin "6") (pinfunction "D_6") (pintype "bidirectional"))
      (node (ref "Q403") (pin "7") (pinfunction "D_7") (pintype "bidirectional"))
      (node (ref "Q403") (pin "8") (pinfunction "D_8") (pintype "bidirectional"))
      (node (ref "Q403") (pin "9") (pinfunction "D_9") (pintype "bidirectional"))
    )
    (net (code "115") (name "Net-(J404-Pad2)") (class "Default")
      (node (ref "J404") (pin "2") (pinfunction "2_2") (pintype "passive"))
      (node (ref "Q404") (pin "5") (pinfunction "D_5") (pintype "bidirectional"))
      (node (ref "Q404") (pin "6") (pinfunction "D_6") (pintype "bidirectional"))
      (node (ref "Q404") (pin "7") (pinfunction "D_7") (pintype "bidirectional"))
      (node (ref "Q404") (pin "8") (pinfunction "D_8") (pintype "bidirectional"))
      (node (ref "Q404") (pin "9") (pinfunction "D_9") (pintype "bidirectional"))
    )
    (net (code "116") (name "Net-(Q101A-D)") (class "Default")
      (node (ref "Q101") (pin "6") (pinfunction "D_6") (pintype "bidirectional"))
      (node (ref "R103") (pin "1") (pinfunction "1_1") (pintype "passive"))
      (node (ref "R105") (pin "2") (pinfunction "2_2") (pintype "passive"))
      (node (ref "R107") (pin "1") (pinfunction "1_1") (pintype "passive"))
    )
    (net (code "117") (name "Net-(Q101B-D)") (class "Default")
      (node (ref "Q101") (pin "4") (pinfunction "D_4") (pintype "passive"))
      (node (ref "R105") (pin "1") (pinfunction "1_1") (pintype "passive"))
    )
    (net (code "118") (name "Net-(Q102A-D)") (class "Default")
      (node (ref "Q102") (pin "6") (pinfunction "D_6") (pintype "bidirectional"))
      (node (ref "R104") (pin "1") (pinfunction "1_1") (pintype "passive"))
      (node (ref "R106") (pin "2") (pinfunction "2_2") (pintype "passive"))
      (node (ref "R108") (pin "1") (pinfunction "1_1") (pintype "passive"))
    )
    (net (code "119") (name "Net-(Q102B-D)") (class "Default")
      (node (ref "Q102") (pin "4") (pinfunction "D_4") (pintype "passive"))
      (node (ref "R106") (pin "1") (pinfunction "1_1") (pintype "passive"))
    )
    (net (code "120") (name "Net-(Q103-G)") (class "Default")
      (node (ref "Q103") (pin "4") (pinfunction "G_4") (pintype "bidirectional"))
      (node (ref "R114") (pin "2") (pinfunction "2_2") (pintype "passive"))
    )
    (net (code "121") (name "Net-(Q104-G)") (class "Default")
      (node (ref "Q104") (pin "4") (pinfunction "G_4") (pintype "bidirectional"))
      (node (ref "R115") (pin "2") (pinfunction "2_2") (pintype "passive"))
    )
    (net (code "122") (name "Net-(Q201A-D)") (class "Default")
      (node (ref "Q201") (pin "6") (pinfunction "D_6") (pintype "bidirectional"))
      (node (ref "R203") (pin "1") (pinfunction "1_1") (pintype "passive"))
      (node (ref "R205") (pin "2") (pinfunction "2_2") (pintype "passive"))
      (node (ref "R207") (pin "1") (pinfunction "1_1") (pintype "passive"))
    )
    (net (code "123") (name "Net-(Q201B-D)") (class "Default")
      (node (ref "Q201") (pin "4") (pinfunction "D_4") (pintype "passive"))
      (node (ref "R205") (pin "1") (pinfunction "1_1") (pintype "passive"))
    )
    (net (code "124") (name "Net-(Q202A-D)") (class "Default")
      (node (ref "Q202") (pin "6") (pinfunction "D_6") (pintype "bidirectional"))
      (node (ref "R204") (pin "1") (pinfunction "1_1") (pintype "passive"))
      (node (ref "R206") (pin "2") (pinfunction "2_2") (pintype "passive"))
      (node (ref "R208") (pin "1") (pinfunction "1_1") (pintype "passive"))
    )
    (net (code "125") (name "Net-(Q202B-D)") (class "Default")
      (node (ref "Q202") (pin "4") (pinfunction "D_4") (pintype "passive"))
      (node (ref "R206") (pin "1") (pinfunction "1_1") (pintype "passive"))
    )
    (net (code "126") (name "Net-(Q203-G)") (class "Default")
      (node (ref "Q203") (pin "4") (pinfunction "G_4") (pintype "bidirectional"))
      (node (ref "R214") (pin "2") (pinfunction "2_2") (pintype "passive"))
    )
    (net (code "127") (name "Net-(Q204-G)") (class "Default")
      (node (ref "Q204") (pin "4") (pinfunction "G_4") (pintype "bidirectional"))
      (node (ref "R215") (pin "2") (pinfunction "2_2") (pintype "passive"))
    )
    (net (code "128") (name "Net-(Q301A-D)") (class "Default")
      (node (ref "Q301") (pin "6") (pinfunction "D_6") (pintype "bidirectional"))
      (node (ref "R303") (pin "1") (pinfunction "1_1") (pintype "passive"))
      (node (ref "R305") (pin "2") (pinfunction "2_2") (pintype "passive"))
      (node (ref "R307") (pin "1") (pinfunction "1_1") (pintype "passive"))
    )
    (net (code "129") (name "Net-(Q301B-D)") (class "Default")
      (node (ref "Q301") (pin "4") (pinfunction "D_4") (pintype "passive"))
      (node (ref "R305") (pin "1") (pinfunction "1_1") (pintype "passive"))
    )
    (net (code "130") (name "Net-(Q302A-D)") (class "Default")
      (node (ref "Q302") (pin "6") (pinfunction "D_6") (pintype "bidirectional"))
      (node (ref "R304") (pin "1") (pinfunction "1_1") (pintype "passive"))
      (node (ref "R306") (pin "2") (pinfunction "2_2") (pintype "passive"))
      (node (ref "R308") (pin "1") (pinfunction "1_1") (pintype "passive"))
    )
    (net (code "131") (name "Net-(Q302B-D)") (class "Default")
      (node (ref "Q302") (pin "4") (pinfunction "D_4") (pintype "passive"))
      (node (ref "R306") (pin "1") (pinfunction "1_1") (pintype "passive"))
    )
    (net (code "132") (name "Net-(Q303-G)") (class "Default")
      (node (ref "Q303") (pin "4") (pinfunction "G_4") (pintype "bidirectional"))
      (node (ref "R314") (pin "2") (pinfunction "2_2") (pintype "passive"))
    )
    (net (code "133") (name "Net-(Q304-G)") (class "Default")
      (node (ref "Q304") (pin "4") (pinfunction "G_4") (pintype "bidirectional"))
      (node (ref "R315") (pin "2") (pinfunction "2_2") (pintype "passive"))
    )
    (net (code "134") (name "Net-(Q401A-D)") (class "Default")
      (node (ref "Q401") (pin "6") (pinfunction "D_6") (pintype "bidirectional"))
      (node (ref "R403") (pin "1") (pinfunction "1_1") (pintype "passive"))
      (node (ref "R405") (pin "2") (pinfunction "2_2") (pintype "passive"))
      (node (ref "R407") (pin "1") (pinfunction "1_1") (pintype "passive"))
    )
    (net (code "135") (name "Net-(Q401B-D)") (class "Default")
      (node (ref "Q401") (pin "4") (pinfunction "D_4") (pintype "passive"))
      (node (ref "R405") (pin "1") (pinfunction "1_1") (pintype "passive"))
    )
    (net (code "136") (name "Net-(Q402A-D)") (class "Default")
      (node (ref "Q402") (pin "6") (pinfunction "D_6") (pintype "bidirectional"))
      (node (ref "R404") (pin "1") (pinfunction "1_1") (pintype "passive"))
      (node (ref "R406") (pin "2") (pinfunction "2_2") (pintype "passive"))
      (node (ref "R408") (pin "1") (pinfunction "1_1") (pintype "passive"))
    )
    (net (code "137") (name "Net-(Q402B-D)") (class "Default")
      (node (ref "Q402") (pin "4") (pinfunction "D_4") (pintype "passive"))
      (node (ref "R406") (pin "1") (pinfunction "1_1") (pintype "passive"))
    )
    (net (code "138") (name "Net-(Q403-G)") (class "Default")
      (node (ref "Q403") (pin "4") (pinfunction "G_4") (pintype "bidirectional"))
      (node (ref "R414") (pin "2") (pinfunction "2_2") (pintype "passive"))
    )
    (net (code "139") (name "Net-(Q404-G)") (class "Default")
      (node (ref "Q404") (pin "4") (pinfunction "G_4") (pintype "bidirectional"))
      (node (ref "R415") (pin "2") (pinfunction "2_2") (pintype "passive"))
    )
    (net (code "140") (name "Net-(R109-END)") (class "Default")
      (node (ref "R107") (pin "2") (pinfunction "2_2") (pintype "passive"))
      (node (ref "R109") (pin "3") (pinfunction "END_3") (pintype "passive"))
    )
    (net (code "141") (name "Net-(R110-END)") (class "Default")
      (node (ref "R108") (pin "2") (pinfunction "2_2") (pintype "passive"))
      (node (ref "R110") (pin "3") (pinfunction "END_3") (pintype "passive"))
    )
    (net (code "142") (name "Net-(R209-END)") (class "Default")
      (node (ref "R207") (pin "2") (pinfunction "2_2") (pintype "passive"))
      (node (ref "R209") (pin "3") (pinfunction "END_3") (pintype "passive"))
    )
    (net (code "143") (name "Net-(R210-END)") (class "Default")
      (node (ref "R208") (pin "2") (pinfunction "2_2") (pintype "passive"))
      (node (ref "R210") (pin "3") (pinfunction "END_3") (pintype "passive"))
    )
    (net (code "144") (name "Net-(R309-END)") (class "Default")
      (node (ref "R307") (pin "2") (pinfunction "2_2") (pintype "passive"))
      (node (ref "R309") (pin "3") (pinfunction "END_3") (pintype "passive"))
    )
    (net (code "145") (name "Net-(R310-END)") (class "Default")
      (node (ref "R308") (pin "2") (pinfunction "2_2") (pintype "passive"))
      (node (ref "R310") (pin "3") (pinfunction "END_3") (pintype "passive"))
    )
    (net (code "146") (name "Net-(R409-END)") (class "Default")
      (node (ref "R407") (pin "2") (pinfunction "2_2") (pintype "passive"))
      (node (ref "R409") (pin "3") (pinfunction "END_3") (pintype "passive"))
    )
    (net (code "147") (name "Net-(R410-END)") (class "Default")
      (node (ref "R408") (pin "2") (pinfunction "2_2") (pintype "passive"))
      (node (ref "R410") (pin "3") (pinfunction "END_3") (pintype "passive"))
    )
    (net (code "148") (name "Net-(Y1A-IO)") (class "Default")
      (node (ref "C16") (pin "2") (pinfunction "2_2") (pintype "bidirectional"))
      (node (ref "R8") (pin "1") (pinfunction "1_1") (pintype "passive"))
      (node (ref "Y1") (pin "1") (pinfunction "IO_1") (pintype "passive"))
    )
    (net (code "149") (name "RST_BUS") (class "Default")
      (node (ref "IC102") (pin "1") (pinfunction "I0_1") (pintype "input"))
      (node (ref "IC102") (pin "2") (pinfunction "I1_2") (pintype "input"))
      (node (ref "IC102") (pin "5") (pinfunction "I0_5") (pintype "input"))
      (node (ref "IC103") (pin "1") (pinfunction "I0_1") (pintype "input"))
      (node (ref "IC103") (pin "2") (pinfunction "I1_2") (pintype "input"))
      (node (ref "IC103") (pin "5") (pinfunction "I0_5") (pintype "input"))
      (node (ref "IC202") (pin "1") (pinfunction "I0_1") (pintype "input"))
      (node (ref "IC202") (pin "2") (pinfunction "I1_2") (pintype "input"))
      (node (ref "IC202") (pin "5") (pinfunction "I0_5") (pintype "input"))
      (node (ref "IC203") (pin "1") (pinfunction "I0_1") (pintype "input"))
      (node (ref "IC203") (pin "2") (pinfunction "I1_2") (pintype "input"))
      (node (ref "IC203") (pin "5") (pinfunction "I0_5") (pintype "input"))
      (node (ref "IC3") (pin "3") (pinfunction "O_3") (pintype "output"))
      (node (ref "IC302") (pin "1") (pinfunction "I0_1") (pintype "input"))
      (node (ref "IC302") (pin "2") (pinfunction "I1_2") (pintype "input"))
      (node (ref "IC302") (pin "5") (pinfunction "I0_5") (pintype "input"))
      (node (ref "IC303") (pin "1") (pinfunction "I0_1") (pintype "input"))
      (node (ref "IC303") (pin "2") (pinfunction "I1_2") (pintype "input"))
      (node (ref "IC303") (pin "5") (pinfunction "I0_5") (pintype "input"))
      (node (ref "IC402") (pin "1") (pinfunction "I0_1") (pintype "input"))
      (node (ref "IC402") (pin "2") (pinfunction "I1_2") (pintype "input"))
      (node (ref "IC402") (pin "5") (pinfunction "I0_5") (pintype "input"))
      (node (ref "IC403") (pin "1") (pinfunction "I0_1") (pintype "input"))
      (node (ref "IC403") (pin "2") (pinfunction "I1_2") (pintype "input"))
      (node (ref "IC403") (pin "5") (pinfunction "I0_5") (pintype "input"))
    )
    (net (code "150") (name "RST_SW") (class "Default")
      (node (ref "J7") (pin "4") (pinfunction "4_4") (pintype "passive"))
      (node (ref "R6") (pin "1") (pinfunction "1_1") (pintype "passive"))
      (node (ref "R7") (pin "1") (pinfunction "1_1") (pintype "passive"))
      (node (ref "S1") (pin "3") (pinfunction "P$2_3") (pintype "passive"))
    )
    (net (code "151") (name "SCK") (class "Default")
      (node (ref "DS1") (pin "7") (pinfunction "DB0_7") (pintype "bidirectional"))
      (node (ref "IC4") (pin "26") (pinfunction "I2C4_SMBA/SPI2_CK/PB13_26") (pintype "bidirectional"))
    )
    (net (code "152") (name "SWCK") (class "Default")
      (node (ref "IC4") (pin "37") (pinfunction "SWCK/JTCK/PA14_37") (pintype "bidirectional"))
      (node (ref "J2") (pin "8") (pinfunction "8_8") (pintype "passive"))
    )
    (net (code "153") (name "SWIO") (class "Default")
      (node (ref "IC4") (pin "34") (pinfunction "SWIO/JTMS/PA13_34") (pintype "bidirectional"))
      (node (ref "J2") (pin "10") (pinfunction "10_10") (pintype "passive"))
    )
    (net (code "154") (name "TRIG_BUS") (class "Default")
      (node (ref "IC102") (pin "6") (pinfunction "I1_6") (pintype "input"))
      (node (ref "IC103") (pin "6") (pinfunction "I1_6") (pintype "input"))
      (node (ref "IC202") (pin "6") (pinfunction "I1_6") (pintype "input"))
      (node (ref "IC203") (pin "6") (pinfunction "I1_6") (pintype "input"))
      (node (ref "IC302") (pin "6") (pinfunction "I1_6") (pintype "input"))
      (node (ref "IC303") (pin "6") (pinfunction "I1_6") (pintype "input"))
      (node (ref "IC402") (pin "6") (pinfunction "I1_6") (pintype "input"))
      (node (ref "IC403") (pin "6") (pinfunction "I1_6") (pintype "input"))
      (node (ref "IC5") (pin "3") (pinfunction "O_3") (pintype "output"))
      (node (ref "J7") (pin "3") (pinfunction "3_3") (pintype "passive"))
    )
    (net (code "155") (name "U6-RX") (class "Default")
      (node (ref "IC4") (pin "33") (pinfunction "USART1_RTS/PA12_33") (pintype "bidirectional"))
      (node (ref "J2") (pin "7") (pinfunction "7_7") (pintype "passive"))
    )
    (net (code "156") (name "U6-TX") (class "Default")
      (node (ref "IC4") (pin "32") (pinfunction "USART1_CTS/PA11_32") (pintype "bidirectional"))
      (node (ref "J2") (pin "3") (pinfunction "3_3") (pintype "passive"))
    )
    (net (code "157") (name "unconnected-(DS1-DB2-Pad9)") (class "Default")
      (node (ref "DS1") (pin "9") (pinfunction "DB2_9") (pintype "bidirectional"))
    )
    (net (code "158") (name "unconnected-(J103-Pad3)") (class "Default")
      (node (ref "J103") (pin "3") (pinfunction "3_3") (pintype "passive"))
    )
    (net (code "159") (name "unconnected-(J103-Pad4)") (class "Default")
      (node (ref "J103") (pin "4") (pinfunction "4_4") (pintype "passive"))
    )
    (net (code "160") (name "unconnected-(J104-Pad3)") (class "Default")
      (node (ref "J104") (pin "3") (pinfunction "3_3") (pintype "passive"))
    )
    (net (code "161") (name "unconnected-(J104-Pad4)") (class "Default")
      (node (ref "J104") (pin "4") (pinfunction "4_4") (pintype "passive"))
    )
    (net (code "162") (name "unconnected-(J203-Pad3)") (class "Default")
      (node (ref "J203") (pin "3") (pinfunction "3_3") (pintype "passive"))
    )
    (net (code "163") (name "unconnected-(J203-Pad4)") (class "Default")
      (node (ref "J203") (pin "4") (pinfunction "4_4") (pintype "passive"))
    )
    (net (code "164") (name "unconnected-(J204-Pad3)") (class "Default")
      (node (ref "J204") (pin "3") (pinfunction "3_3") (pintype "passive"))
    )
    (net (code "165") (name "unconnected-(J204-Pad4)") (class "Default")
      (node (ref "J204") (pin "4") (pinfunction "4_4") (pintype "passive"))
    )
    (net (code "166") (name "unconnected-(J303-Pad3)") (class "Default")
      (node (ref "J303") (pin "3") (pinfunction "3_3") (pintype "passive"))
    )
    (net (code "167") (name "unconnected-(J303-Pad4)") (class "Default")
      (node (ref "J303") (pin "4") (pinfunction "4_4") (pintype "passive"))
    )
    (net (code "168") (name "unconnected-(J304-Pad3)") (class "Default")
      (node (ref "J304") (pin "3") (pinfunction "3_3") (pintype "passive"))
    )
    (net (code "169") (name "unconnected-(J304-Pad4)") (class "Default")
      (node (ref "J304") (pin "4") (pinfunction "4_4") (pintype "passive"))
    )
    (net (code "170") (name "unconnected-(J403-Pad3)") (class "Default")
      (node (ref "J403") (pin "3") (pinfunction "3_3") (pintype "passive"))
    )
    (net (code "171") (name "unconnected-(J403-Pad4)") (class "Default")
      (node (ref "J403") (pin "4") (pinfunction "4_4") (pintype "passive"))
    )
    (net (code "172") (name "unconnected-(J404-Pad3)") (class "Default")
      (node (ref "J404") (pin "3") (pinfunction "3_3") (pintype "passive"))
    )
    (net (code "173") (name "unconnected-(J404-Pad4)") (class "Default")
      (node (ref "J404") (pin "4") (pinfunction "4_4") (pintype "passive"))
    )
    (net (code "174") (name "~{CS}") (class "Default")
      (node (ref "DS1") (pin "17") (pinfunction "~{CS}_17") (pintype "bidirectional"))
      (node (ref "IC4") (pin "25") (pinfunction "SPI2_CS/PB12_25") (pintype "bidirectional"))
    )
    (net (code "175") (name "~{D_RES}") (class "Default")
      (node (ref "DS1") (pin "16") (pinfunction "~{RES}_16") (pintype "bidirectional"))
      (node (ref "IC4") (pin "21") (pinfunction "PB10_21") (pintype "bidirectional"))
    )
  )
)
